# ISA_XILINX.net
KiCad netlist of a schematic drawn in Altium Designer
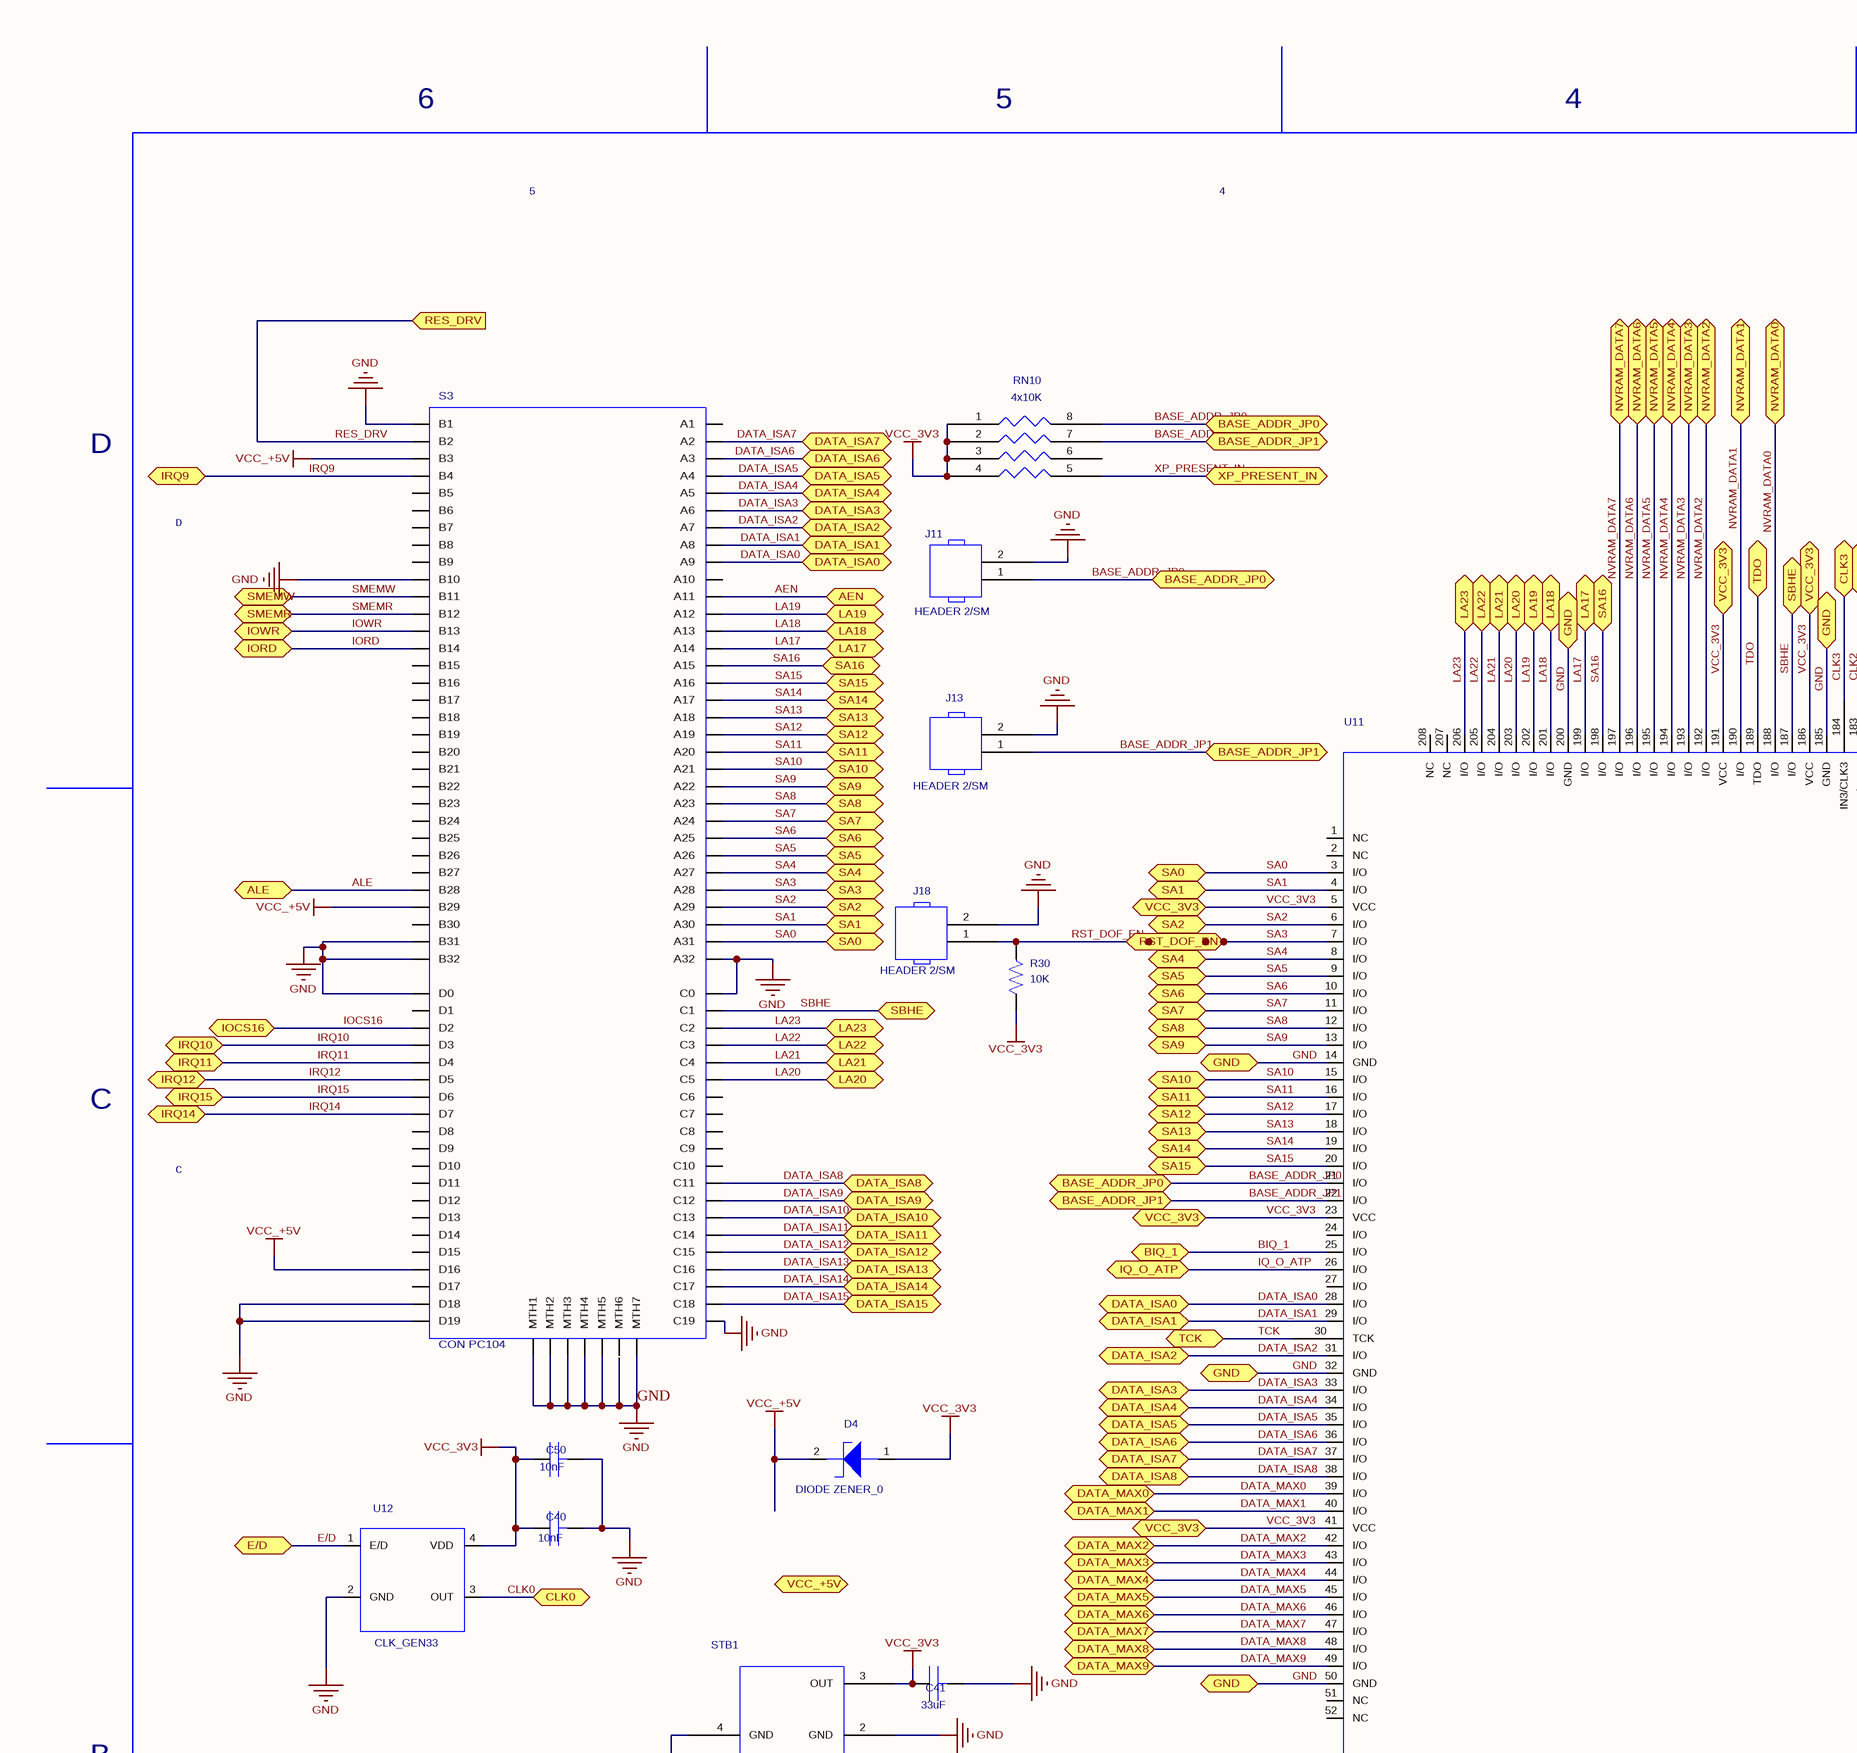
[diagram p0: ISA_XILINX.SchDoc, top left]
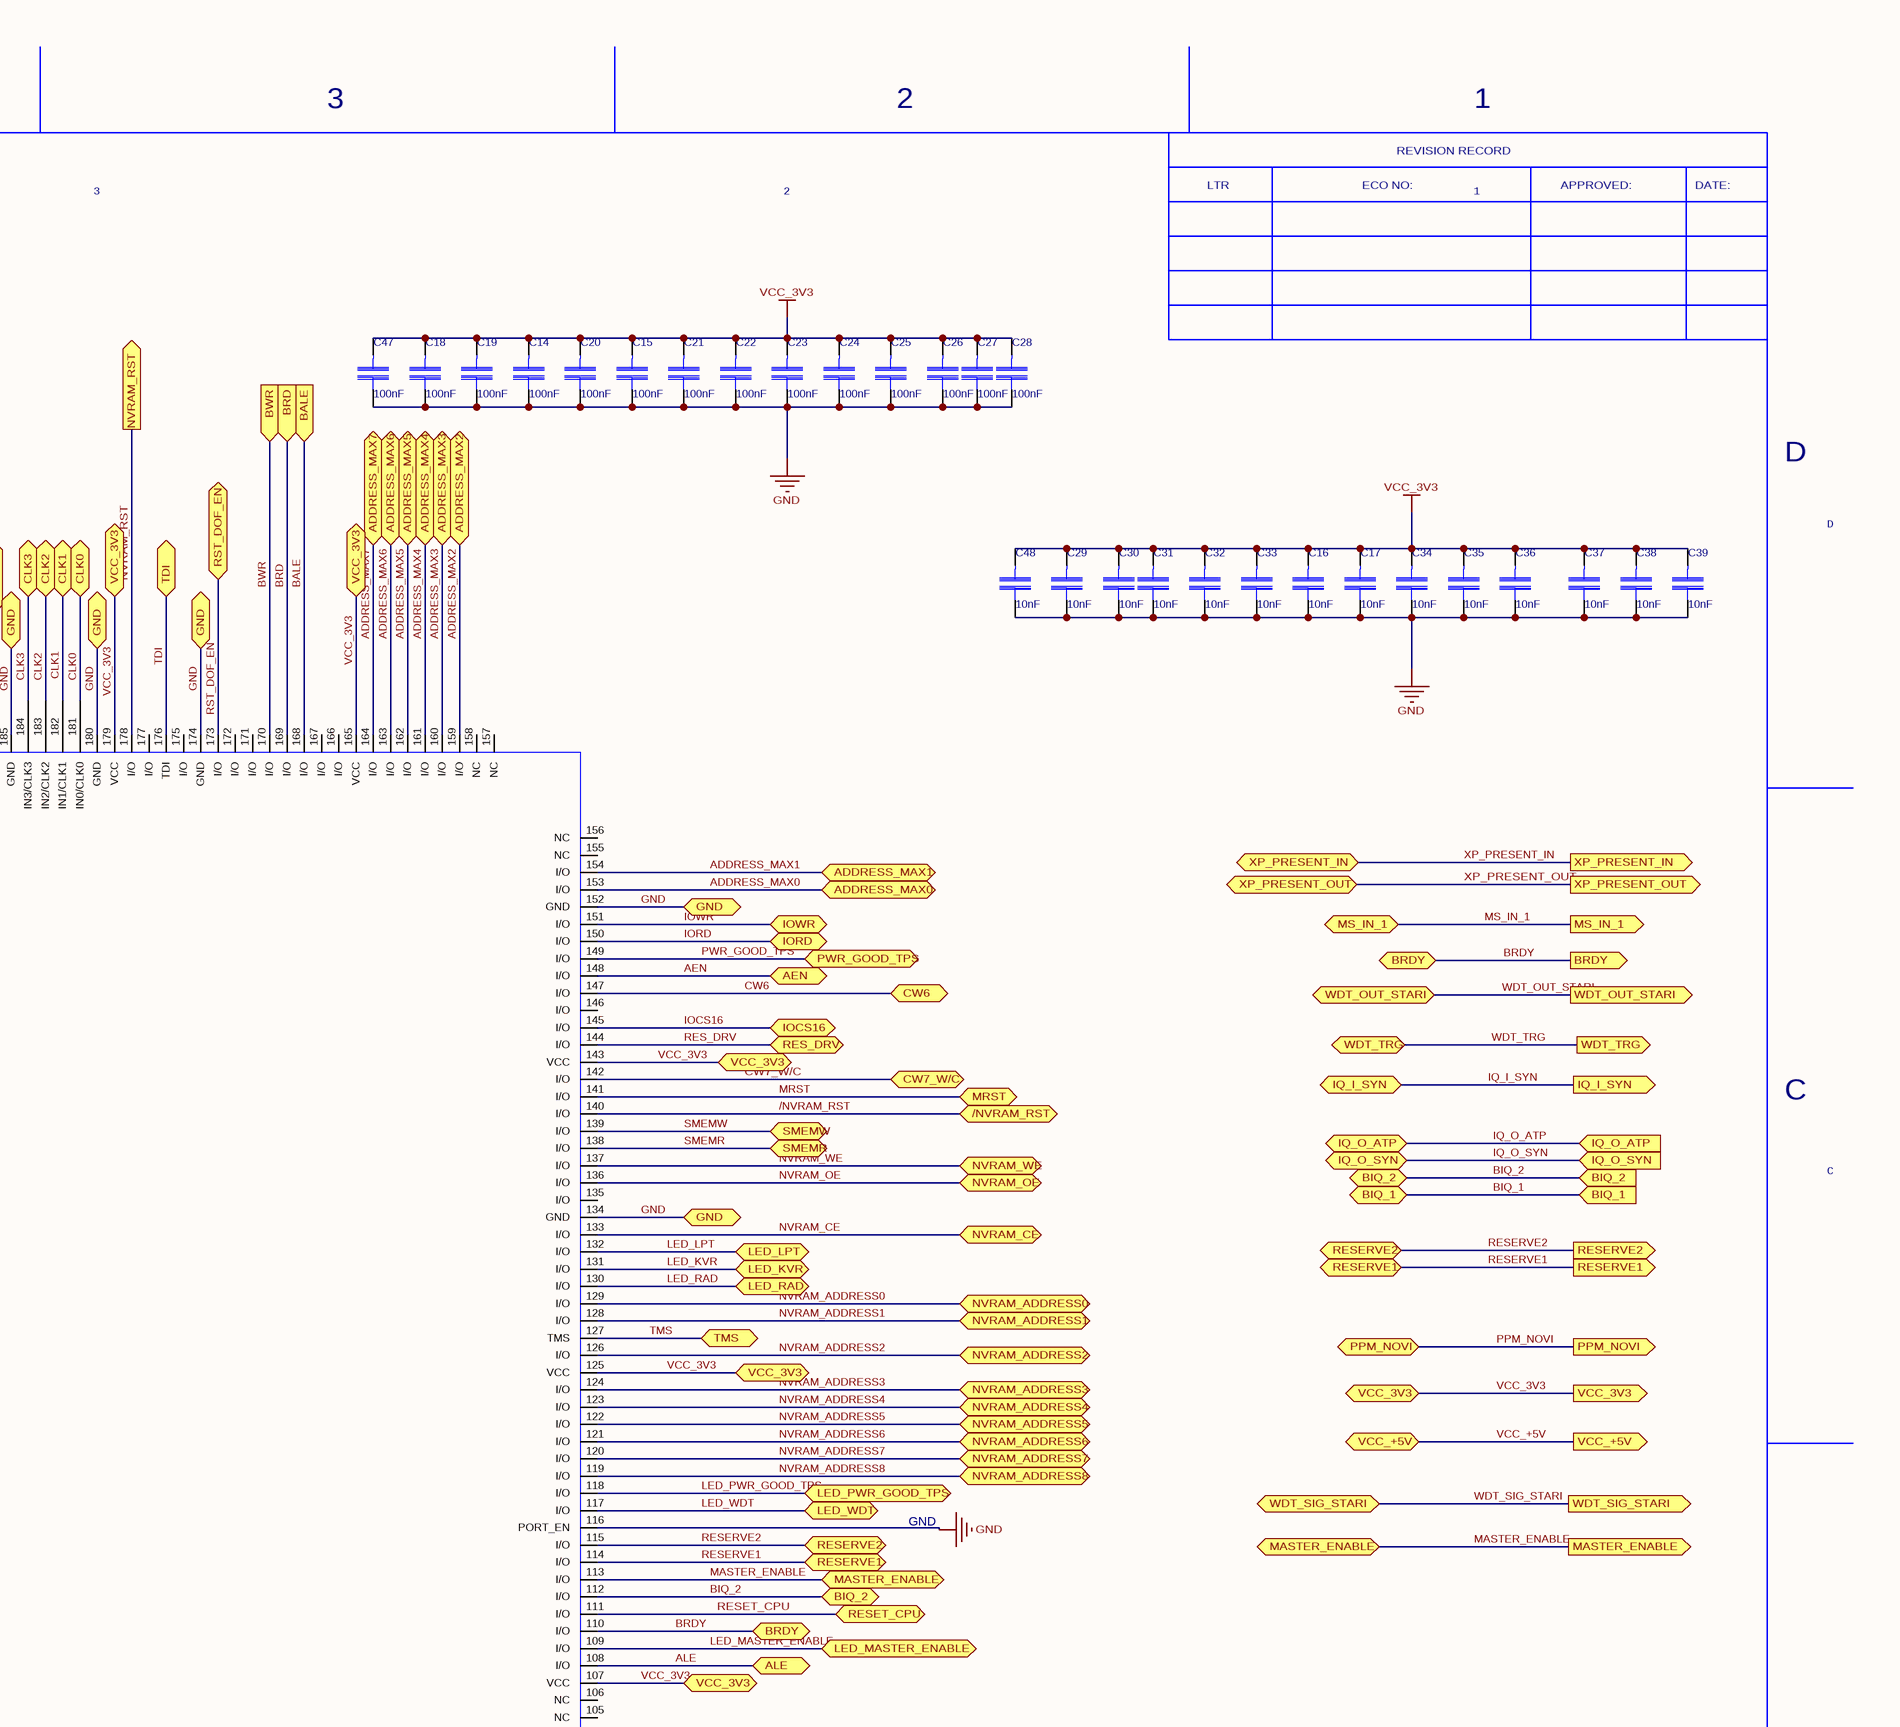
[diagram p1: ISA_XILINX.SchDoc, top right]
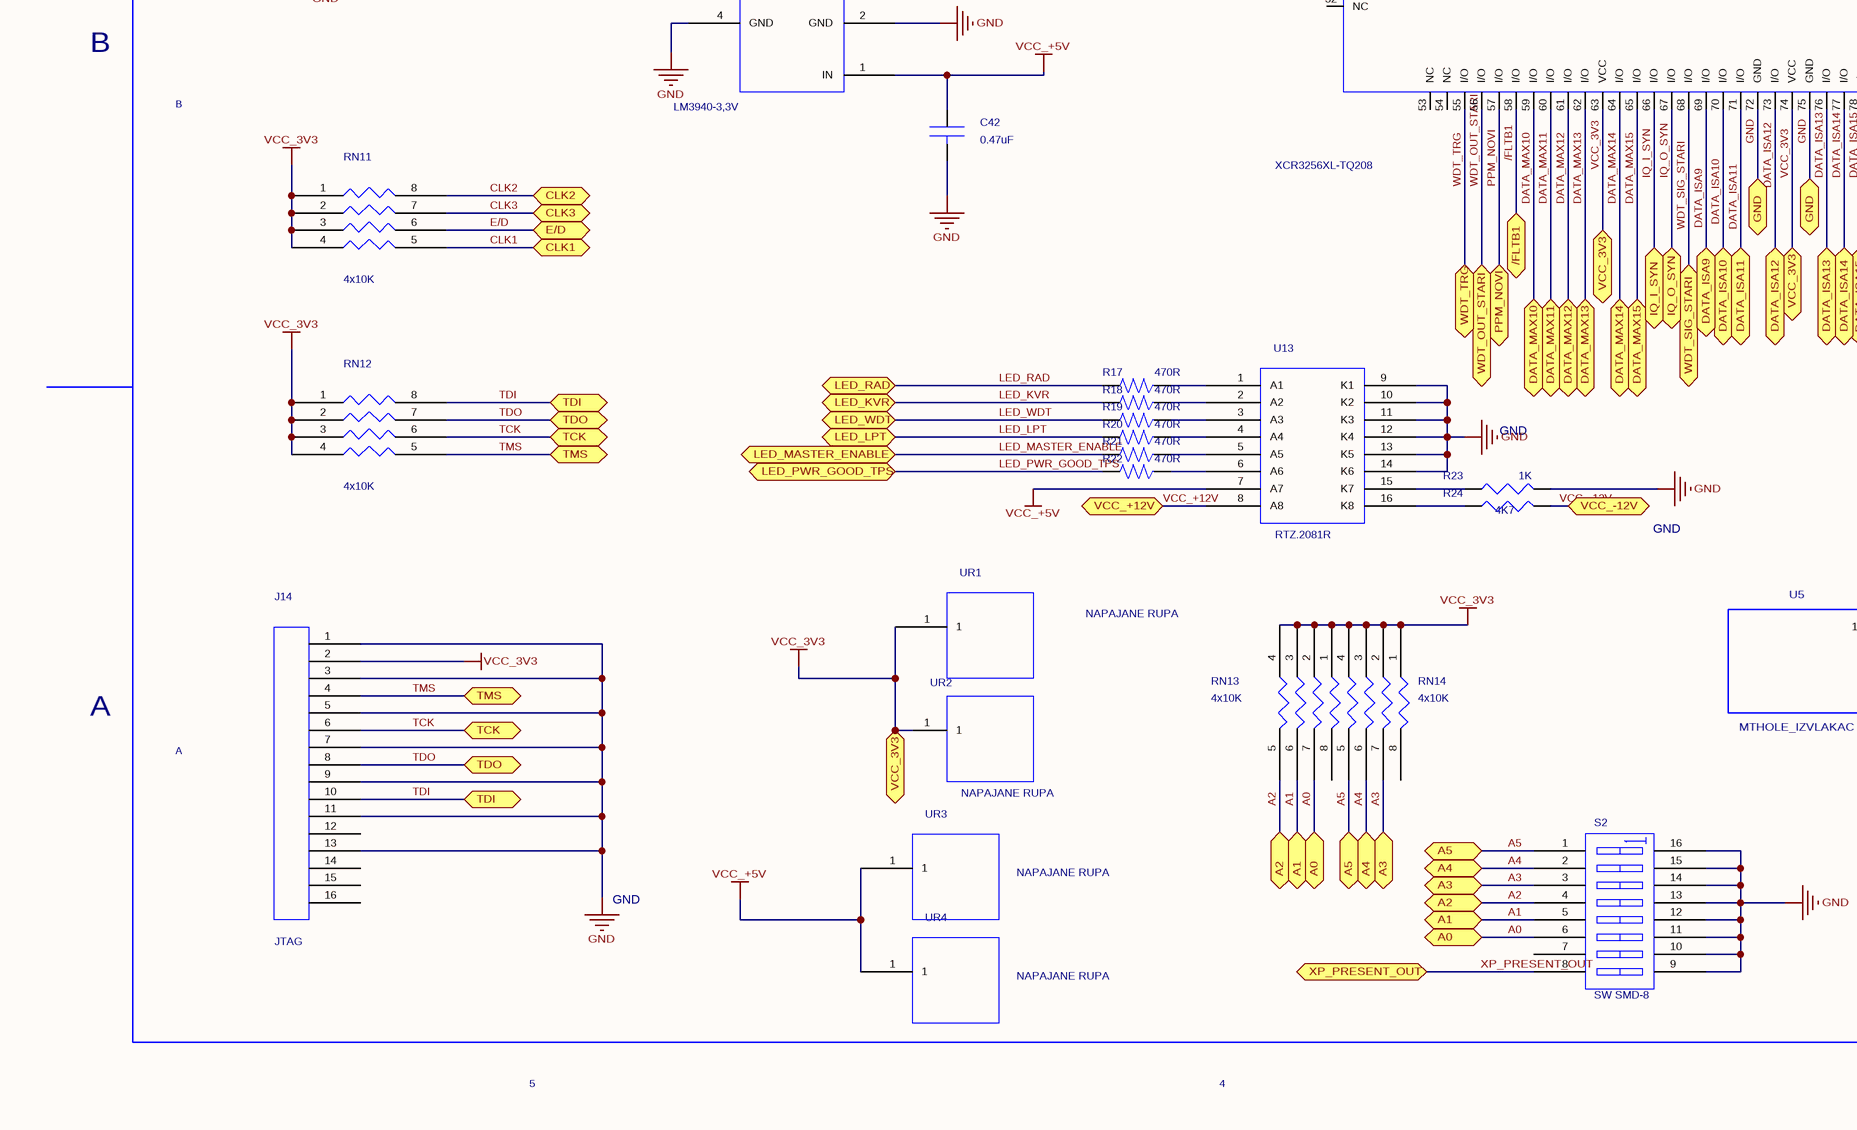
[diagram p2: ISA_XILINX.SchDoc, bottom left]
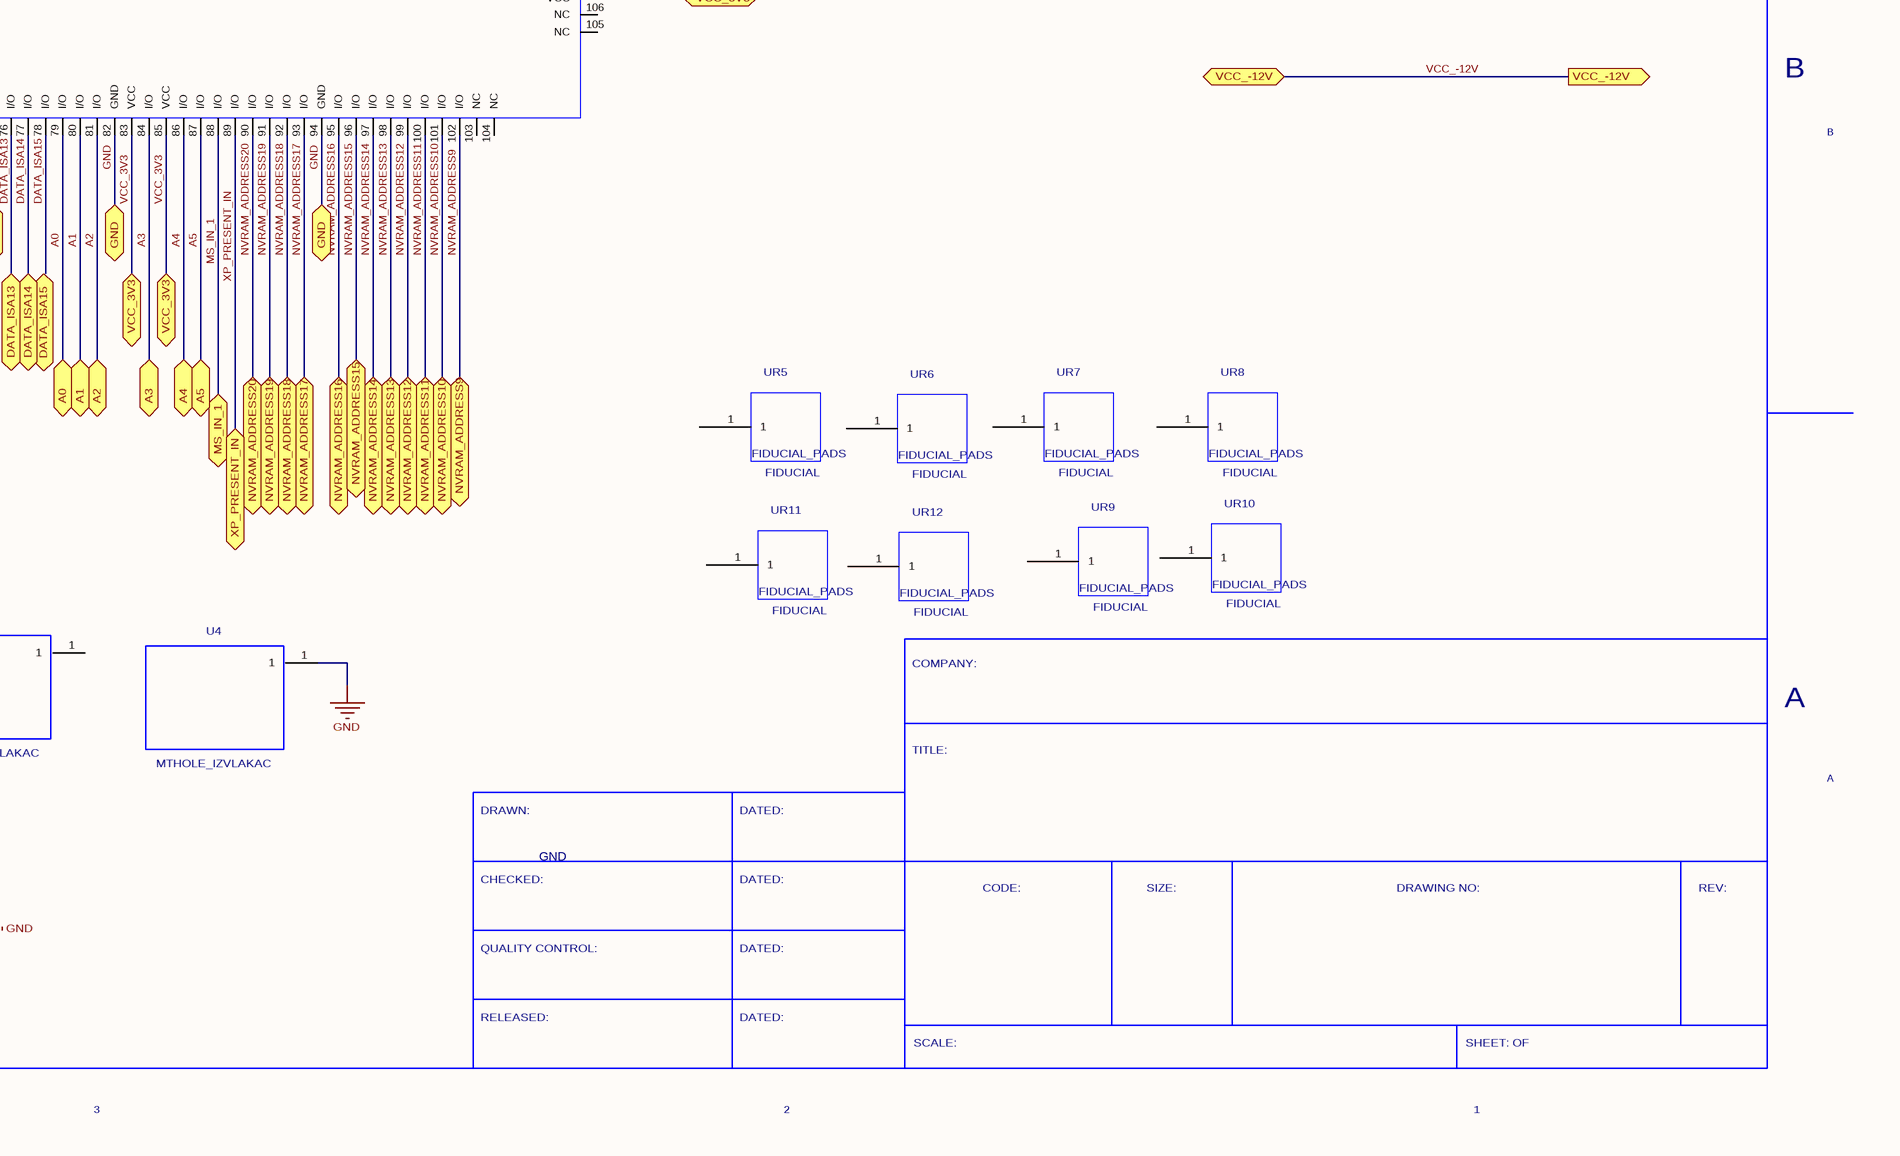
[diagram p3: ISA_XILINX.SchDoc, bottom right]

(export (version "E")
  (design (tool "Eeschema 10.0.6"))
  (components
    (comp (ref "C14")
      (value "100nF")
      (footprint "SM/C_0805")
      (fields (field (name "Comment") "C"))
      (libsource (lib "*") (part "C"))
    )
    (comp (ref "C15")
      (value "100nF")
      (footprint "SM/C_0805")
      (fields (field (name "Comment") "C"))
      (libsource (lib "*") (part "C"))
    )
    (comp (ref "C16")
      (value "10nF")
      (footprint "SM/C_0805")
      (fields (field (name "Comment") "C"))
      (libsource (lib "*") (part "C"))
    )
    (comp (ref "C17")
      (value "10nF")
      (footprint "SM/C_0805")
      (fields (field (name "Comment") "C"))
      (libsource (lib "*") (part "C"))
    )
    (comp (ref "C18")
      (value "100nF")
      (footprint "SM/C_0805")
      (fields (field (name "Comment") "C"))
      (libsource (lib "*") (part "C"))
    )
    (comp (ref "C19")
      (value "100nF")
      (footprint "SM/C_0805")
      (fields (field (name "Comment") "C"))
      (libsource (lib "*") (part "C"))
    )
    (comp (ref "C20")
      (value "100nF")
      (footprint "SM/C_0805")
      (fields (field (name "Comment") "C"))
      (libsource (lib "*") (part "C"))
    )
    (comp (ref "C21")
      (value "100nF")
      (footprint "SM/C_0805")
      (fields (field (name "Comment") "C"))
      (libsource (lib "*") (part "C"))
    )
    (comp (ref "C22")
      (value "100nF")
      (footprint "SM/C_0805")
      (fields (field (name "Comment") "C"))
      (libsource (lib "*") (part "C"))
    )
    (comp (ref "C23")
      (value "100nF")
      (footprint "SM/C_0805")
      (fields (field (name "Comment") "C"))
      (libsource (lib "*") (part "C"))
    )
    (comp (ref "C24")
      (value "100nF")
      (footprint "SM/C_0805")
      (fields (field (name "Comment") "C"))
      (libsource (lib "*") (part "C"))
    )
    (comp (ref "C25")
      (value "100nF")
      (footprint "SM/C_0805")
      (fields (field (name "Comment") "C"))
      (libsource (lib "*") (part "C"))
    )
    (comp (ref "C26")
      (value "100nF")
      (footprint "SM/C_0805")
      (fields (field (name "Comment") "C"))
      (libsource (lib "*") (part "C"))
    )
    (comp (ref "C27")
      (value "100nF")
      (footprint "SM/C_0805")
      (fields (field (name "Comment") "C"))
      (libsource (lib "*") (part "C"))
    )
    (comp (ref "C28")
      (value "100nF")
      (footprint "SM/C_0805")
      (fields (field (name "Comment") "C"))
      (libsource (lib "*") (part "C"))
    )
    (comp (ref "C29")
      (value "10nF")
      (footprint "SM/C_0805")
      (fields (field (name "Comment") "C"))
      (libsource (lib "*") (part "C"))
    )
    (comp (ref "C30")
      (value "10nF")
      (footprint "SM/C_0805")
      (fields (field (name "Comment") "C"))
      (libsource (lib "*") (part "C"))
    )
    (comp (ref "C31")
      (value "10nF")
      (footprint "SM/C_0805")
      (fields (field (name "Comment") "C"))
      (libsource (lib "*") (part "C"))
    )
    (comp (ref "C32")
      (value "10nF")
      (footprint "SM/C_0805")
      (fields (field (name "Comment") "C"))
      (libsource (lib "*") (part "C"))
    )
    (comp (ref "C33")
      (value "10nF")
      (footprint "SM/C_0805")
      (fields (field (name "Comment") "C"))
      (libsource (lib "*") (part "C"))
    )
    (comp (ref "C34")
      (value "10nF")
      (footprint "SM/C_0805")
      (fields (field (name "Comment") "C"))
      (libsource (lib "*") (part "C"))
    )
    (comp (ref "C35")
      (value "10nF")
      (footprint "SM/C_0805")
      (fields (field (name "Comment") "C"))
      (libsource (lib "*") (part "C"))
    )
    (comp (ref "C36")
      (value "10nF")
      (footprint "SM/C_0805")
      (fields (field (name "Comment") "C"))
      (libsource (lib "*") (part "C"))
    )
    (comp (ref "C37")
      (value "10nF")
      (footprint "SM/C_0805")
      (fields (field (name "Comment") "C"))
      (libsource (lib "*") (part "C"))
    )
    (comp (ref "C38")
      (value "10nF")
      (footprint "SM/C_0805")
      (fields (field (name "Comment") "C"))
      (libsource (lib "*") (part "C"))
    )
    (comp (ref "C39")
      (value "10nF")
      (footprint "SM/C_0805")
      (fields (field (name "Comment") "C"))
      (libsource (lib "*") (part "C"))
    )
    (comp (ref "C40")
      (value "10nF")
      (footprint "SM/C_0805")
      (fields (field (name "Comment") "C_4"))
      (libsource (lib "*") (part "C_4"))
    )
    (comp (ref "C41")
      (value "33uF")
      (footprint "CASE_D_MILOS")
      (fields (field (name "Comment") "C_4"))
      (libsource (lib "*") (part "C_4"))
    )
    (comp (ref "C42")
      (value "0.47uF")
      (footprint "CASE_B_MILOS")
      (fields (field (name "Comment") "C_4"))
      (libsource (lib "*") (part "C_4"))
    )
    (comp (ref "C47")
      (value "100nF")
      (footprint "SM/C_0805")
      (fields (field (name "Comment") "C"))
      (libsource (lib "*") (part "C"))
    )
    (comp (ref "C48")
      (value "10nF")
      (footprint "SM/C_0805")
      (fields (field (name "Comment") "C"))
      (libsource (lib "*") (part "C"))
    )
    (comp (ref "C50")
      (value "10nF")
      (footprint "SM/C_0805")
      (fields (field (name "Comment") "C_4"))
      (libsource (lib "*") (part "C_4"))
    )
    (comp (ref "D4")
      (value "DIODE ZENER_0")
      (footprint "BZV55-C3V3")
      (fields (field (name "Comment") "DIODE_ZENER_1"))
      (libsource (lib "*") (part "DIODE_ZENER_1"))
    )
    (comp (ref "J11")
      (value "HEADER 2/SM")
      (footprint "JUMPER_100")
      (fields (field (name "Comment") "HEADER_2/SM"))
      (libsource (lib "*") (part "HEADER_2/SM"))
    )
    (comp (ref "J13")
      (value "HEADER 2/SM")
      (footprint "JUMPER_100")
      (fields (field (name "Comment") "HEADER_2/SM"))
      (libsource (lib "*") (part "HEADER_2/SM"))
    )
    (comp (ref "J14")
      (value "JTAG")
      (footprint "JTAG_SMD_REV2")
      (fields (field (name "Comment") "CONN_FLEX_16/SM"))
      (libsource (lib "*") (part "CONN_FLEX_16/SM"))
    )
    (comp (ref "J18")
      (value "HEADER 2/SM")
      (footprint "JUMPER_100")
      (fields (field (name "Comment") "HEADER_2/SM"))
      (libsource (lib "*") (part "HEADER_2/SM"))
    )
    (comp (ref "R17")
      (value "470R")
      (footprint "SM/R_1206")
      (fields (field (name "VOLTAGE") "RVMAX") (field (name "POWER") "RMAX") (field (name "Comment") "R"))
      (libsource (lib "*") (part "R"))
    )
    (comp (ref "R18")
      (value "470R")
      (footprint "SM/R_1206")
      (fields (field (name "VOLTAGE") "RVMAX") (field (name "POWER") "RMAX") (field (name "Comment") "R"))
      (libsource (lib "*") (part "R"))
    )
    (comp (ref "R19")
      (value "470R")
      (footprint "SM/R_1206")
      (fields (field (name "VOLTAGE") "RVMAX") (field (name "POWER") "RMAX") (field (name "Comment") "R"))
      (libsource (lib "*") (part "R"))
    )
    (comp (ref "R20")
      (value "470R")
      (footprint "SM/R_1206")
      (fields (field (name "VOLTAGE") "RVMAX") (field (name "POWER") "RMAX") (field (name "Comment") "R"))
      (libsource (lib "*") (part "R"))
    )
    (comp (ref "R21")
      (value "470R")
      (footprint "SM/R_1206")
      (fields (field (name "VOLTAGE") "RVMAX") (field (name "POWER") "RMAX") (field (name "Comment") "R"))
      (libsource (lib "*") (part "R"))
    )
    (comp (ref "R22")
      (value "470R")
      (footprint "SM/R_1206")
      (fields (field (name "VOLTAGE") "RVMAX") (field (name "POWER") "RMAX") (field (name "Comment") "R"))
      (libsource (lib "*") (part "R"))
    )
    (comp (ref "R23")
      (value "1K")
      (footprint "SM/R_1206")
      (fields (field (name "Comment") "RESISTOR_2"))
      (libsource (lib "*") (part "RESISTOR_2"))
    )
    (comp (ref "R24")
      (value "4K7")
      (footprint "SM/R_1206")
      (fields (field (name "Comment") "RESISTOR_2"))
      (libsource (lib "*") (part "RESISTOR_2"))
    )
    (comp (ref "R30")
      (value "10K")
      (footprint "SM/R_1206")
      (fields (field (name "VOLTAGE") "RVMAX") (field (name "POWER") "RMAX") (field (name "Comment") "R"))
      (libsource (lib "*") (part "R"))
    )
    (comp (ref "RN10")
      (value "4x10K")
      (footprint "SMD_RX4")
      (fields (field (name "Comment") "RESAR_IS_4/SM"))
      (libsource (lib "*") (part "RESAR_IS_4/SM"))
    )
    (comp (ref "RN11")
      (value "4x10K")
      (footprint "SMD_RX4")
      (fields (field (name "Comment") "RESAR_IS_4/SM"))
      (libsource (lib "*") (part "RESAR_IS_4/SM"))
    )
    (comp (ref "RN12")
      (value "4x10K")
      (footprint "SMD_RX4")
      (fields (field (name "Comment") "RESAR_IS_4/SM"))
      (libsource (lib "*") (part "RESAR_IS_4/SM"))
    )
    (comp (ref "RN13")
      (value "4x10K")
      (footprint "SMD_RX4")
      (fields (field (name "Comment") "RESAR_IS_4/SM"))
      (libsource (lib "*") (part "RESAR_IS_4/SM"))
    )
    (comp (ref "RN14")
      (value "4x10K")
      (footprint "SMD_RX4")
      (fields (field (name "Comment") "RESAR_IS_4/SM"))
      (libsource (lib "*") (part "RESAR_IS_4/SM"))
    )
    (comp (ref "S2")
      (value "SW SMD-8")
      (footprint "SMD_DIPSW_100")
      (fields (field (name "Comment") "SW_DIP-8"))
      (libsource (lib "*") (part "SW_DIP-8"))
    )
    (comp (ref "S3")
      (value "CON PC104")
      (footprint "WAFER_PADS_REV2")
      (fields (field (name "Comment") "CON_EISAE_0"))
      (libsource (lib "ATLAS_XP2V5.2016.11.14") (part "CON_EISAE_0"))
    )
    (comp (ref "STB1")
      (value "LM3940-3,3V")
      (footprint "TO263AA_GND_PLANE_REV1")
      (fields (field (name "Comment") "LM3940-3_3V"))
      (libsource (lib "*") (part "LM3940-3_3V"))
    )
    (comp (ref "U4")
      (value "MTHOLE_IZVLAKAC")
      (footprint "MTH_IZVLAKAC_PADS")
      (description "Rupa za Rittal-ov izvlakac")
      (libsource (lib "*") (part "MTHOLE_IZVLAKAC"))
    )
    (comp (ref "U5")
      (value "MTHOLE_IZVLAKAC")
      (footprint "MTH_IZVLAKAC_PADS")
      (description "Rupa za Rittal-ov izvlakac")
      (libsource (lib "*") (part "MTHOLE_IZVLAKAC"))
    )
    (comp (ref "U11")
      (value "XCR3256XL-TQ208")
      (footprint "QUAD.50M/208/WG30.60")
      (libsource (lib "*") (part "XCR3256XL-TQ208"))
    )
    (comp (ref "U12")
      (value "CLK_GEN33")
      (footprint "CLK_GEN33_REV1")
      (libsource (lib "*") (part "CLK_GEN33"))
    )
    (comp (ref "U13")
      (value "RTZ.2081R")
      (footprint "LED_8_REV3_PADS")
      (description "LED8x1")
      (fields (field (name "Comment") "LED8X1"))
      (libsource (lib "*") (part "LED8X1"))
    )
    (comp (ref "UR1")
      (value "NAPAJANE RUPA")
      (footprint "NAPAJANJE_RUPA_REV1")
      (fields (field (name "Comment") "NAPAJANE_RUPA"))
      (libsource (lib "*") (part "NAPAJANE_RUPA"))
    )
    (comp (ref "UR2")
      (value "NAPAJANE RUPA")
      (footprint "NAPAJANJE_RUPA_REV1")
      (fields (field (name "Comment") "NAPAJANE_RUPA"))
      (libsource (lib "*") (part "NAPAJANE_RUPA"))
    )
    (comp (ref "UR3")
      (value "NAPAJANE RUPA")
      (footprint "NAPAJANJE_RUPA_REV1")
      (fields (field (name "Comment") "NAPAJANE_RUPA"))
      (libsource (lib "*") (part "NAPAJANE_RUPA"))
    )
    (comp (ref "UR4")
      (value "NAPAJANE RUPA")
      (footprint "NAPAJANJE_RUPA_REV1")
      (fields (field (name "Comment") "NAPAJANE_RUPA"))
      (libsource (lib "*") (part "NAPAJANE_RUPA"))
    )
    (comp (ref "UR5")
      (value "FIDUCIAL_PADS")
      (footprint "FIDUCIAL_R_TOP")
      (fields (field (name "ALTIUM_VALUE") "FIDUCIAL"))
      (libsource (lib "*") (part "FIDUCIAL_PADS"))
    )
    (comp (ref "UR6")
      (value "FIDUCIAL_PADS")
      (footprint "FIDUCIAL_R_TOP")
      (fields (field (name "ALTIUM_VALUE") "FIDUCIAL"))
      (libsource (lib "*") (part "FIDUCIAL_PADS"))
    )
    (comp (ref "UR7")
      (value "FIDUCIAL_PADS")
      (footprint "FIDUCIAL_R_TOP")
      (fields (field (name "ALTIUM_VALUE") "FIDUCIAL"))
      (libsource (lib "*") (part "FIDUCIAL_PADS"))
    )
    (comp (ref "UR8")
      (value "FIDUCIAL_PADS")
      (footprint "FIDUCIAL_R_TOP")
      (fields (field (name "ALTIUM_VALUE") "FIDUCIAL"))
      (libsource (lib "*") (part "FIDUCIAL_PADS"))
    )
    (comp (ref "UR9")
      (value "FIDUCIAL_PADS")
      (footprint "FIDUCIAL_R_TOP")
      (fields (field (name "ALTIUM_VALUE") "FIDUCIAL"))
      (libsource (lib "*") (part "FIDUCIAL_PADS"))
    )
    (comp (ref "UR10")
      (value "FIDUCIAL_PADS")
      (footprint "FIDUCIAL_R_TOP")
      (fields (field (name "ALTIUM_VALUE") "FIDUCIAL"))
      (libsource (lib "*") (part "FIDUCIAL_PADS"))
    )
    (comp (ref "UR11")
      (value "FIDUCIAL_PADS")
      (footprint "FIDUCIAL_R_TOP")
      (fields (field (name "ALTIUM_VALUE") "FIDUCIAL"))
      (libsource (lib "*") (part "FIDUCIAL_PADS"))
    )
    (comp (ref "UR12")
      (value "FIDUCIAL_PADS")
      (footprint "FIDUCIAL_R_TOP")
      (fields (field (name "ALTIUM_VALUE") "FIDUCIAL"))
      (libsource (lib "*") (part "FIDUCIAL_PADS"))
    )
  )
  (nets
    (net (code "1") (name "/A0") (class "Default")
      (node (ref "RN13") (pin "7") (pinfunction "7_7") (pintype "passive"))
      (node (ref "S2") (pin "6") (pinfunction "A6_6") (pintype "passive"))
      (node (ref "U11") (pin "79") (pinfunction "I/O_79") (pintype "bidirectional"))
    )
    (net (code "2") (name "/A1") (class "Default")
      (node (ref "RN13") (pin "6") (pinfunction "6_6") (pintype "passive"))
      (node (ref "S2") (pin "5") (pinfunction "A5_5") (pintype "passive"))
      (node (ref "U11") (pin "80") (pinfunction "I/O_80") (pintype "bidirectional"))
    )
    (net (code "3") (name "/A2") (class "Default")
      (node (ref "RN13") (pin "5") (pinfunction "5_5") (pintype "passive"))
      (node (ref "S2") (pin "4") (pinfunction "A4_4") (pintype "passive"))
      (node (ref "U11") (pin "81") (pinfunction "I/O_81") (pintype "bidirectional"))
    )
    (net (code "4") (name "/A3") (class "Default")
      (node (ref "RN14") (pin "7") (pinfunction "7_7") (pintype "passive"))
      (node (ref "S2") (pin "3") (pinfunction "A3_3") (pintype "passive"))
      (node (ref "U11") (pin "84") (pinfunction "I/O_84") (pintype "bidirectional"))
    )
    (net (code "5") (name "/A4") (class "Default")
      (node (ref "RN14") (pin "6") (pinfunction "6_6") (pintype "passive"))
      (node (ref "S2") (pin "2") (pinfunction "A2_2") (pintype "passive"))
      (node (ref "U11") (pin "86") (pinfunction "I/O_86") (pintype "bidirectional"))
    )
    (net (code "6") (name "/A5") (class "Default")
      (node (ref "RN14") (pin "5") (pinfunction "5_5") (pintype "passive"))
      (node (ref "S2") (pin "1") (pinfunction "A1_1") (pintype "passive"))
      (node (ref "U11") (pin "87") (pinfunction "I/O_87") (pintype "bidirectional"))
    )
    (net (code "7") (name "/ADDRESS_MAX0") (class "Default")
      (node (ref "U11") (pin "153") (pinfunction "I/O_153") (pintype "bidirectional"))
    )
    (net (code "8") (name "/ADDRESS_MAX1") (class "Default")
      (node (ref "U11") (pin "154") (pinfunction "I/O_154") (pintype "bidirectional"))
    )
    (net (code "9") (name "/ADDRESS_MAX2") (class "Default")
      (node (ref "U11") (pin "159") (pinfunction "I/O_159") (pintype "bidirectional"))
    )
    (net (code "10") (name "/ADDRESS_MAX3") (class "Default")
      (node (ref "U11") (pin "160") (pinfunction "I/O_160") (pintype "bidirectional"))
    )
    (net (code "11") (name "/ADDRESS_MAX4") (class "Default")
      (node (ref "U11") (pin "161") (pinfunction "I/O_161") (pintype "bidirectional"))
    )
    (net (code "12") (name "/ADDRESS_MAX5") (class "Default")
      (node (ref "U11") (pin "162") (pinfunction "I/O_162") (pintype "bidirectional"))
    )
    (net (code "13") (name "/ADDRESS_MAX6") (class "Default")
      (node (ref "U11") (pin "163") (pinfunction "I/O_163") (pintype "bidirectional"))
    )
    (net (code "14") (name "/ADDRESS_MAX7") (class "Default")
      (node (ref "U11") (pin "164") (pinfunction "I/O_164") (pintype "bidirectional"))
    )
    (net (code "15") (name "/AEN") (class "Default")
      (node (ref "S3") (pin "A11") (pinfunction "A11_A11") (pintype "passive"))
      (node (ref "U11") (pin "148") (pinfunction "I/O_148") (pintype "bidirectional"))
    )
    (net (code "16") (name "/ALE") (class "Default")
      (node (ref "S3") (pin "B28") (pinfunction "B28_B28") (pintype "passive"))
      (node (ref "U11") (pin "108") (pinfunction "I/O_108") (pintype "bidirectional"))
    )
    (net (code "17") (name "/BALE") (class "Default")
      (node (ref "U11") (pin "168") (pinfunction "I/O_168") (pintype "bidirectional"))
    )
    (net (code "18") (name "/BASE_ADDR_JP0") (class "Default")
      (node (ref "J11") (pin "1") (pinfunction "1_1") (pintype "passive"))
      (node (ref "RN10") (pin "8") (pinfunction "8_8") (pintype "passive"))
      (node (ref "U11") (pin "21") (pinfunction "I/O_21") (pintype "bidirectional"))
    )
    (net (code "19") (name "/BASE_ADDR_JP1") (class "Default")
      (node (ref "J13") (pin "1") (pinfunction "1_1") (pintype "passive"))
      (node (ref "RN10") (pin "7") (pinfunction "7_7") (pintype "passive"))
      (node (ref "U11") (pin "22") (pinfunction "I/O_22") (pintype "bidirectional"))
    )
    (net (code "20") (name "/BIQ_1") (class "Default")
      (node (ref "U11") (pin "25") (pinfunction "I/O_25") (pintype "bidirectional"))
    )
    (net (code "21") (name "/BIQ_2") (class "Default")
      (node (ref "U11") (pin "112") (pinfunction "I/O_112") (pintype "bidirectional"))
    )
    (net (code "22") (name "/BRD") (class "Default")
      (node (ref "U11") (pin "169") (pinfunction "I/O_169") (pintype "bidirectional"))
    )
    (net (code "23") (name "/BRDY") (class "Default")
      (node (ref "U11") (pin "110") (pinfunction "I/O_110") (pintype "bidirectional"))
    )
    (net (code "24") (name "/BWR") (class "Default")
      (node (ref "U11") (pin "170") (pinfunction "I/O_170") (pintype "bidirectional"))
    )
    (net (code "25") (name "/CLK0") (class "Default")
      (node (ref "U11") (pin "181") (pinfunction "IN0/CLK0_181") (pintype "passive"))
      (node (ref "U12") (pin "3") (pinfunction "OUT_3") (pintype "passive"))
    )
    (net (code "26") (name "/CLK1") (class "Default")
      (node (ref "RN11") (pin "5") (pinfunction "5_5") (pintype "passive"))
      (node (ref "U11") (pin "182") (pinfunction "IN1/CLK1_182") (pintype "passive"))
    )
    (net (code "27") (name "/CLK2") (class "Default")
      (node (ref "RN11") (pin "8") (pinfunction "8_8") (pintype "passive"))
      (node (ref "U11") (pin "183") (pinfunction "IN2/CLK2_183") (pintype "passive"))
    )
    (net (code "28") (name "/CLK3") (class "Default")
      (node (ref "RN11") (pin "7") (pinfunction "7_7") (pintype "passive"))
      (node (ref "U11") (pin "184") (pinfunction "IN3/CLK3_184") (pintype "passive"))
    )
    (net (code "29") (name "/CW6") (class "Default")
      (node (ref "U11") (pin "147") (pinfunction "I/O_147") (pintype "bidirectional"))
    )
    (net (code "30") (name "/CW7_W{slash}C") (class "Default")
      (node (ref "U11") (pin "142") (pinfunction "I/O_142") (pintype "bidirectional"))
    )
    (net (code "31") (name "/DATA_ISA0") (class "Default")
      (node (ref "S3") (pin "A9") (pinfunction "A9_A9") (pintype "passive"))
      (node (ref "U11") (pin "28") (pinfunction "I/O_28") (pintype "bidirectional"))
    )
    (net (code "32") (name "/DATA_ISA1") (class "Default")
      (node (ref "S3") (pin "A8") (pinfunction "A8_A8") (pintype "passive"))
      (node (ref "U11") (pin "29") (pinfunction "I/O_29") (pintype "bidirectional"))
    )
    (net (code "33") (name "/DATA_ISA2") (class "Default")
      (node (ref "S3") (pin "A7") (pinfunction "A7_A7") (pintype "passive"))
      (node (ref "U11") (pin "31") (pinfunction "I/O_31") (pintype "bidirectional"))
    )
    (net (code "34") (name "/DATA_ISA3") (class "Default")
      (node (ref "S3") (pin "A6") (pinfunction "A6_A6") (pintype "passive"))
      (node (ref "U11") (pin "33") (pinfunction "I/O_33") (pintype "bidirectional"))
    )
    (net (code "35") (name "/DATA_ISA4") (class "Default")
      (node (ref "S3") (pin "A5") (pinfunction "A5_A5") (pintype "passive"))
      (node (ref "U11") (pin "34") (pinfunction "I/O_34") (pintype "bidirectional"))
    )
    (net (code "36") (name "/DATA_ISA5") (class "Default")
      (node (ref "S3") (pin "A4") (pinfunction "A4_A4") (pintype "passive"))
      (node (ref "U11") (pin "35") (pinfunction "I/O_35") (pintype "bidirectional"))
    )
    (net (code "37") (name "/DATA_ISA6") (class "Default")
      (node (ref "S3") (pin "A3") (pinfunction "A3_A3") (pintype "passive"))
      (node (ref "U11") (pin "36") (pinfunction "I/O_36") (pintype "bidirectional"))
    )
    (net (code "38") (name "/DATA_ISA7") (class "Default")
      (node (ref "S3") (pin "A2") (pinfunction "A2_A2") (pintype "passive"))
      (node (ref "U11") (pin "37") (pinfunction "I/O_37") (pintype "bidirectional"))
    )
    (net (code "39") (name "/DATA_ISA8") (class "Default")
      (node (ref "S3") (pin "C11") (pinfunction "C11_C11") (pintype "passive"))
      (node (ref "U11") (pin "38") (pinfunction "I/O_38") (pintype "bidirectional"))
    )
    (net (code "40") (name "/DATA_ISA9") (class "Default")
      (node (ref "S3") (pin "C12") (pinfunction "C12_C12") (pintype "passive"))
      (node (ref "U11") (pin "69") (pinfunction "I/O_69") (pintype "bidirectional"))
    )
    (net (code "41") (name "/DATA_ISA10") (class "Default")
      (node (ref "S3") (pin "C13") (pinfunction "C13_C13") (pintype "passive"))
      (node (ref "U11") (pin "70") (pinfunction "I/O_70") (pintype "bidirectional"))
    )
    (net (code "42") (name "/DATA_ISA11") (class "Default")
      (node (ref "S3") (pin "C14") (pinfunction "C14_C14") (pintype "passive"))
      (node (ref "U11") (pin "71") (pinfunction "I/O_71") (pintype "bidirectional"))
    )
    (net (code "43") (name "/DATA_ISA12") (class "Default")
      (node (ref "S3") (pin "C15") (pinfunction "C15_C15") (pintype "passive"))
      (node (ref "U11") (pin "73") (pinfunction "I/O_73") (pintype "bidirectional"))
    )
    (net (code "44") (name "/DATA_ISA13") (class "Default")
      (node (ref "S3") (pin "C16") (pinfunction "C16_C16") (pintype "passive"))
      (node (ref "U11") (pin "76") (pinfunction "I/O_76") (pintype "bidirectional"))
    )
    (net (code "45") (name "/DATA_ISA14") (class "Default")
      (node (ref "S3") (pin "C17") (pinfunction "C17_C17") (pintype "passive"))
      (node (ref "U11") (pin "77") (pinfunction "I/O_77") (pintype "bidirectional"))
    )
    (net (code "46") (name "/DATA_ISA15") (class "Default")
      (node (ref "S3") (pin "C18") (pinfunction "C18_C18") (pintype "passive"))
      (node (ref "U11") (pin "78") (pinfunction "I/O_78") (pintype "bidirectional"))
    )
    (net (code "47") (name "/DATA_MAX0") (class "Default")
      (node (ref "U11") (pin "39") (pinfunction "I/O_39") (pintype "bidirectional"))
    )
    (net (code "48") (name "/DATA_MAX1") (class "Default")
      (node (ref "U11") (pin "40") (pinfunction "I/O_40") (pintype "bidirectional"))
    )
    (net (code "49") (name "/DATA_MAX2") (class "Default")
      (node (ref "U11") (pin "42") (pinfunction "I/O_42") (pintype "bidirectional"))
    )
    (net (code "50") (name "/DATA_MAX3") (class "Default")
      (node (ref "U11") (pin "43") (pinfunction "I/O_43") (pintype "bidirectional"))
    )
    (net (code "51") (name "/DATA_MAX4") (class "Default")
      (node (ref "U11") (pin "44") (pinfunction "I/O_44") (pintype "bidirectional"))
    )
    (net (code "52") (name "/DATA_MAX5") (class "Default")
      (node (ref "U11") (pin "45") (pinfunction "I/O_45") (pintype "bidirectional"))
    )
    (net (code "53") (name "/DATA_MAX6") (class "Default")
      (node (ref "U11") (pin "46") (pinfunction "I/O_46") (pintype "bidirectional"))
    )
    (net (code "54") (name "/DATA_MAX7") (class "Default")
      (node (ref "U11") (pin "47") (pinfunction "I/O_47") (pintype "bidirectional"))
    )
    (net (code "55") (name "/DATA_MAX8") (class "Default")
      (node (ref "U11") (pin "48") (pinfunction "I/O_48") (pintype "bidirectional"))
    )
    (net (code "56") (name "/DATA_MAX9") (class "Default")
      (node (ref "U11") (pin "49") (pinfunction "I/O_49") (pintype "bidirectional"))
    )
    (net (code "57") (name "/DATA_MAX10") (class "Default")
      (node (ref "U11") (pin "59") (pinfunction "I/O_59") (pintype "bidirectional"))
    )
    (net (code "58") (name "/DATA_MAX11") (class "Default")
      (node (ref "U11") (pin "60") (pinfunction "I/O_60") (pintype "bidirectional"))
    )
    (net (code "59") (name "/DATA_MAX12") (class "Default")
      (node (ref "U11") (pin "61") (pinfunction "I/O_61") (pintype "bidirectional"))
    )
    (net (code "60") (name "/DATA_MAX13") (class "Default")
      (node (ref "U11") (pin "62") (pinfunction "I/O_62") (pintype "bidirectional"))
    )
    (net (code "61") (name "/DATA_MAX14") (class "Default")
      (node (ref "U11") (pin "64") (pinfunction "I/O_64") (pintype "bidirectional"))
    )
    (net (code "62") (name "/DATA_MAX15") (class "Default")
      (node (ref "U11") (pin "65") (pinfunction "I/O_65") (pintype "bidirectional"))
    )
    (net (code "63") (name "/E{slash}D") (class "Default")
      (node (ref "RN11") (pin "6") (pinfunction "6_6") (pintype "passive"))
      (node (ref "U12") (pin "1") (pinfunction "E/D_1") (pintype "passive"))
    )
    (net (code "64") (name "/IOCS16") (class "Default")
      (node (ref "S3") (pin "D2") (pinfunction "D2_D2") (pintype "passive"))
      (node (ref "U11") (pin "145") (pinfunction "I/O_145") (pintype "bidirectional"))
    )
    (net (code "65") (name "/IORD") (class "Default")
      (node (ref "S3") (pin "B14") (pinfunction "B14_B14") (pintype "passive"))
      (node (ref "U11") (pin "150") (pinfunction "I/O_150") (pintype "bidirectional"))
    )
    (net (code "66") (name "/IOWR") (class "Default")
      (node (ref "S3") (pin "B13") (pinfunction "B13_B13") (pintype "passive"))
      (node (ref "U11") (pin "151") (pinfunction "I/O_151") (pintype "bidirectional"))
    )
    (net (code "67") (name "/IQ_I_SYN") (class "Default")
      (node (ref "U11") (pin "66") (pinfunction "I/O_66") (pintype "bidirectional"))
    )
    (net (code "68") (name "/IQ_O_ATP") (class "Default")
      (node (ref "U11") (pin "26") (pinfunction "I/O_26") (pintype "bidirectional"))
    )
    (net (code "69") (name "/IQ_O_SYN") (class "Default")
      (node (ref "U11") (pin "67") (pinfunction "I/O_67") (pintype "bidirectional"))
    )
    (net (code "70") (name "/IRQ9") (class "Default")
      (node (ref "S3") (pin "B4") (pinfunction "B4_B4") (pintype "passive"))
    )
    (net (code "71") (name "/IRQ10") (class "Default")
      (node (ref "S3") (pin "D3") (pinfunction "D3_D3") (pintype "passive"))
    )
    (net (code "72") (name "/IRQ11") (class "Default")
      (node (ref "S3") (pin "D4") (pinfunction "D4_D4") (pintype "passive"))
    )
    (net (code "73") (name "/IRQ12") (class "Default")
      (node (ref "S3") (pin "D5") (pinfunction "D5_D5") (pintype "passive"))
    )
    (net (code "74") (name "/IRQ14") (class "Default")
      (node (ref "S3") (pin "D7") (pinfunction "D7_D7") (pintype "passive"))
    )
    (net (code "75") (name "/IRQ15") (class "Default")
      (node (ref "S3") (pin "D6") (pinfunction "D6_D6") (pintype "passive"))
    )
    (net (code "76") (name "/LA17") (class "Default")
      (node (ref "S3") (pin "A14") (pinfunction "A14_A14") (pintype "passive"))
      (node (ref "U11") (pin "199") (pinfunction "I/O_199") (pintype "bidirectional"))
    )
    (net (code "77") (name "/LA18") (class "Default")
      (node (ref "S3") (pin "A13") (pinfunction "A13_A13") (pintype "passive"))
      (node (ref "U11") (pin "201") (pinfunction "I/O_201") (pintype "bidirectional"))
    )
    (net (code "78") (name "/LA19") (class "Default")
      (node (ref "S3") (pin "A12") (pinfunction "A12_A12") (pintype "passive"))
      (node (ref "U11") (pin "202") (pinfunction "I/O_202") (pintype "bidirectional"))
    )
    (net (code "79") (name "/LA20") (class "Default")
      (node (ref "S3") (pin "C5") (pinfunction "C5_C5") (pintype "passive"))
      (node (ref "U11") (pin "203") (pinfunction "I/O_203") (pintype "bidirectional"))
    )
    (net (code "80") (name "/LA21") (class "Default")
      (node (ref "S3") (pin "C4") (pinfunction "C4_C4") (pintype "passive"))
      (node (ref "U11") (pin "204") (pinfunction "I/O_204") (pintype "bidirectional"))
    )
    (net (code "81") (name "/LA22") (class "Default")
      (node (ref "S3") (pin "C3") (pinfunction "C3_C3") (pintype "passive"))
      (node (ref "U11") (pin "205") (pinfunction "I/O_205") (pintype "bidirectional"))
    )
    (net (code "82") (name "/LA23") (class "Default")
      (node (ref "S3") (pin "C2") (pinfunction "C2_C2") (pintype "passive"))
      (node (ref "U11") (pin "206") (pinfunction "I/O_206") (pintype "bidirectional"))
    )
    (net (code "83") (name "/LED_KVR") (class "Default")
      (node (ref "R18") (pin "2") (pinfunction "2_2") (pintype "passive"))
      (node (ref "U11") (pin "131") (pinfunction "I/O_131") (pintype "bidirectional"))
    )
    (net (code "84") (name "/LED_LPT") (class "Default")
      (node (ref "R20") (pin "2") (pinfunction "2_2") (pintype "passive"))
      (node (ref "U11") (pin "132") (pinfunction "I/O_132") (pintype "bidirectional"))
    )
    (net (code "85") (name "/LED_MASTER_ENABLE") (class "Default")
      (node (ref "R21") (pin "2") (pinfunction "2_2") (pintype "passive"))
      (node (ref "U11") (pin "109") (pinfunction "I/O_109") (pintype "bidirectional"))
    )
    (net (code "86") (name "/LED_PWR_GOOD_TPS") (class "Default")
      (node (ref "R22") (pin "2") (pinfunction "2_2") (pintype "passive"))
      (node (ref "U11") (pin "118") (pinfunction "I/O_118") (pintype "bidirectional"))
    )
    (net (code "87") (name "/LED_RAD") (class "Default")
      (node (ref "R17") (pin "2") (pinfunction "2_2") (pintype "passive"))
      (node (ref "U11") (pin "130") (pinfunction "I/O_130") (pintype "bidirectional"))
    )
    (net (code "88") (name "/LED_WDT") (class "Default")
      (node (ref "R19") (pin "2") (pinfunction "2_2") (pintype "passive"))
      (node (ref "U11") (pin "117") (pinfunction "I/O_117") (pintype "bidirectional"))
    )
    (net (code "89") (name "/MASTER_ENABLE") (class "Default")
      (node (ref "U11") (pin "113") (pinfunction "I/O_113") (pintype "bidirectional"))
    )
    (net (code "90") (name "/MRST") (class "Default")
      (node (ref "U11") (pin "141") (pinfunction "I/O_141") (pintype "bidirectional"))
    )
    (net (code "91") (name "/MS_IN_1") (class "Default")
      (node (ref "U11") (pin "88") (pinfunction "I/O_88") (pintype "bidirectional"))
    )
    (net (code "92") (name "/NVRAM_ADDRESS0") (class "Default")
      (node (ref "U11") (pin "129") (pinfunction "I/O_129") (pintype "bidirectional"))
    )
    (net (code "93") (name "/NVRAM_ADDRESS1") (class "Default")
      (node (ref "U11") (pin "128") (pinfunction "I/O_128") (pintype "bidirectional"))
    )
    (net (code "94") (name "/NVRAM_ADDRESS2") (class "Default")
      (node (ref "U11") (pin "126") (pinfunction "I/O_126") (pintype "bidirectional"))
    )
    (net (code "95") (name "/NVRAM_ADDRESS3") (class "Default")
      (node (ref "U11") (pin "124") (pinfunction "I/O_124") (pintype "bidirectional"))
    )
    (net (code "96") (name "/NVRAM_ADDRESS4") (class "Default")
      (node (ref "U11") (pin "123") (pinfunction "I/O_123") (pintype "bidirectional"))
    )
    (net (code "97") (name "/NVRAM_ADDRESS5") (class "Default")
      (node (ref "U11") (pin "122") (pinfunction "I/O_122") (pintype "bidirectional"))
    )
    (net (code "98") (name "/NVRAM_ADDRESS6") (class "Default")
      (node (ref "U11") (pin "121") (pinfunction "I/O_121") (pintype "bidirectional"))
    )
    (net (code "99") (name "/NVRAM_ADDRESS7") (class "Default")
      (node (ref "U11") (pin "120") (pinfunction "I/O_120") (pintype "bidirectional"))
    )
    (net (code "100") (name "/NVRAM_ADDRESS8") (class "Default")
      (node (ref "U11") (pin "119") (pinfunction "I/O_119") (pintype "bidirectional"))
    )
    (net (code "101") (name "/NVRAM_ADDRESS9") (class "Default")
      (node (ref "U11") (pin "102") (pinfunction "I/O_102") (pintype "bidirectional"))
    )
    (net (code "102") (name "/NVRAM_ADDRESS10") (class "Default")
      (node (ref "U11") (pin "101") (pinfunction "I/O_101") (pintype "bidirectional"))
    )
    (net (code "103") (name "/NVRAM_ADDRESS11") (class "Default")
      (node (ref "U11") (pin "100") (pinfunction "I/O_100") (pintype "bidirectional"))
    )
    (net (code "104") (name "/NVRAM_ADDRESS12") (class "Default")
      (node (ref "U11") (pin "99") (pinfunction "I/O_99") (pintype "bidirectional"))
    )
    (net (code "105") (name "/NVRAM_ADDRESS13") (class "Default")
      (node (ref "U11") (pin "98") (pinfunction "I/O_98") (pintype "bidirectional"))
    )
    (net (code "106") (name "/NVRAM_ADDRESS14") (class "Default")
      (node (ref "U11") (pin "97") (pinfunction "I/O_97") (pintype "bidirectional"))
    )
    (net (code "107") (name "/NVRAM_ADDRESS15") (class "Default")
      (node (ref "U11") (pin "96") (pinfunction "I/O_96") (pintype "bidirectional"))
    )
    (net (code "108") (name "/NVRAM_ADDRESS16") (class "Default")
      (node (ref "U11") (pin "95") (pinfunction "I/O_95") (pintype "bidirectional"))
    )
    (net (code "109") (name "/NVRAM_ADDRESS17") (class "Default")
      (node (ref "U11") (pin "93") (pinfunction "I/O_93") (pintype "bidirectional"))
    )
    (net (code "110") (name "/NVRAM_ADDRESS18") (class "Default")
      (node (ref "U11") (pin "92") (pinfunction "I/O_92") (pintype "bidirectional"))
    )
    (net (code "111") (name "/NVRAM_ADDRESS19") (class "Default")
      (node (ref "U11") (pin "91") (pinfunction "I/O_91") (pintype "bidirectional"))
    )
    (net (code "112") (name "/NVRAM_ADDRESS20") (class "Default")
      (node (ref "U11") (pin "90") (pinfunction "I/O_90") (pintype "bidirectional"))
    )
    (net (code "113") (name "/NVRAM_CE") (class "Default")
      (node (ref "U11") (pin "133") (pinfunction "I/O_133") (pintype "bidirectional"))
    )
    (net (code "114") (name "/NVRAM_DATA0") (class "Default")
      (node (ref "U11") (pin "188") (pinfunction "I/O_188") (pintype "bidirectional"))
    )
    (net (code "115") (name "/NVRAM_DATA1") (class "Default")
      (node (ref "U11") (pin "190") (pinfunction "I/O_190") (pintype "bidirectional"))
    )
    (net (code "116") (name "/NVRAM_DATA2") (class "Default")
      (node (ref "U11") (pin "192") (pinfunction "I/O_192") (pintype "bidirectional"))
    )
    (net (code "117") (name "/NVRAM_DATA3") (class "Default")
      (node (ref "U11") (pin "193") (pinfunction "I/O_193") (pintype "bidirectional"))
    )
    (net (code "118") (name "/NVRAM_DATA4") (class "Default")
      (node (ref "U11") (pin "194") (pinfunction "I/O_194") (pintype "bidirectional"))
    )
    (net (code "119") (name "/NVRAM_DATA5") (class "Default")
      (node (ref "U11") (pin "195") (pinfunction "I/O_195") (pintype "bidirectional"))
    )
    (net (code "120") (name "/NVRAM_DATA6") (class "Default")
      (node (ref "U11") (pin "196") (pinfunction "I/O_196") (pintype "bidirectional"))
    )
    (net (code "121") (name "/NVRAM_DATA7") (class "Default")
      (node (ref "U11") (pin "197") (pinfunction "I/O_197") (pintype "bidirectional"))
    )
    (net (code "122") (name "/NVRAM_OE") (class "Default")
      (node (ref "U11") (pin "136") (pinfunction "I/O_136") (pintype "bidirectional"))
    )
    (net (code "123") (name "/NVRAM_RST") (class "Default")
      (node (ref "U11") (pin "178") (pinfunction "I/O_178") (pintype "bidirectional"))
    )
    (net (code "124") (name "/NVRAM_WE") (class "Default")
      (node (ref "U11") (pin "137") (pinfunction "I/O_137") (pintype "bidirectional"))
    )
    (net (code "125") (name "/PPM_NOVI") (class "Default")
      (node (ref "U11") (pin "57") (pinfunction "I/O_57") (pintype "bidirectional"))
    )
    (net (code "126") (name "/PWR_GOOD_TPS") (class "Default")
      (node (ref "U11") (pin "149") (pinfunction "I/O_149") (pintype "bidirectional"))
    )
    (net (code "127") (name "/RESERVE1") (class "Default")
      (node (ref "U11") (pin "114") (pinfunction "I/O_114") (pintype "bidirectional"))
    )
    (net (code "128") (name "/RESERVE2") (class "Default")
      (node (ref "U11") (pin "115") (pinfunction "I/O_115") (pintype "bidirectional"))
    )
    (net (code "129") (name "/RESET_CPU") (class "Default")
      (node (ref "U11") (pin "111") (pinfunction "I/O_111") (pintype "bidirectional"))
    )
    (net (code "130") (name "/RES_DRV") (class "Default")
      (node (ref "S3") (pin "B2") (pinfunction "B2_B2") (pintype "passive"))
      (node (ref "U11") (pin "144") (pinfunction "I/O_144") (pintype "bidirectional"))
    )
    (net (code "131") (name "/RST_DOF_EN") (class "Default")
      (node (ref "J18") (pin "1") (pinfunction "1_1") (pintype "passive"))
      (node (ref "R30") (pin "1") (pinfunction "1_1") (pintype "passive"))
      (node (ref "S3") (pin "A28") (pinfunction "A28_A28") (pintype "passive"))
      (node (ref "U11") (pin "173") (pinfunction "I/O_173") (pintype "bidirectional"))
      (node (ref "U11") (pin "7") (pinfunction "I/O_7") (pintype "bidirectional"))
    )
    (net (code "132") (name "/SA0") (class "Default")
      (node (ref "S3") (pin "A31") (pinfunction "A31_A31") (pintype "passive"))
      (node (ref "U11") (pin "3") (pinfunction "I/O_3") (pintype "bidirectional"))
    )
    (net (code "133") (name "/SA1") (class "Default")
      (node (ref "S3") (pin "A30") (pinfunction "A30_A30") (pintype "passive"))
      (node (ref "U11") (pin "4") (pinfunction "I/O_4") (pintype "bidirectional"))
    )
    (net (code "134") (name "/SA2") (class "Default")
      (node (ref "S3") (pin "A29") (pinfunction "A29_A29") (pintype "passive"))
      (node (ref "U11") (pin "6") (pinfunction "I/O_6") (pintype "bidirectional"))
    )
    (net (code "135") (name "/SA4") (class "Default")
      (node (ref "S3") (pin "A27") (pinfunction "A27_A27") (pintype "passive"))
      (node (ref "U11") (pin "8") (pinfunction "I/O_8") (pintype "bidirectional"))
    )
    (net (code "136") (name "/SA5") (class "Default")
      (node (ref "S3") (pin "A26") (pinfunction "A26_A26") (pintype "passive"))
      (node (ref "U11") (pin "9") (pinfunction "I/O_9") (pintype "bidirectional"))
    )
    (net (code "137") (name "/SA6") (class "Default")
      (node (ref "S3") (pin "A25") (pinfunction "A25_A25") (pintype "passive"))
      (node (ref "U11") (pin "10") (pinfunction "I/O_10") (pintype "bidirectional"))
    )
    (net (code "138") (name "/SA7") (class "Default")
      (node (ref "S3") (pin "A24") (pinfunction "A24_A24") (pintype "passive"))
      (node (ref "U11") (pin "11") (pinfunction "I/O_11") (pintype "bidirectional"))
    )
    (net (code "139") (name "/SA8") (class "Default")
      (node (ref "S3") (pin "A23") (pinfunction "A23_A23") (pintype "passive"))
      (node (ref "U11") (pin "12") (pinfunction "I/O_12") (pintype "bidirectional"))
    )
    (net (code "140") (name "/SA9") (class "Default")
      (node (ref "S3") (pin "A22") (pinfunction "A22_A22") (pintype "passive"))
      (node (ref "U11") (pin "13") (pinfunction "I/O_13") (pintype "bidirectional"))
    )
    (net (code "141") (name "/SA10") (class "Default")
      (node (ref "S3") (pin "A21") (pinfunction "A21_A21") (pintype "passive"))
      (node (ref "U11") (pin "15") (pinfunction "I/O_15") (pintype "bidirectional"))
    )
    (net (code "142") (name "/SA11") (class "Default")
      (node (ref "S3") (pin "A20") (pinfunction "A20_A20") (pintype "passive"))
      (node (ref "U11") (pin "16") (pinfunction "I/O_16") (pintype "bidirectional"))
    )
    (net (code "143") (name "/SA12") (class "Default")
      (node (ref "S3") (pin "A19") (pinfunction "A19_A19") (pintype "passive"))
      (node (ref "U11") (pin "17") (pinfunction "I/O_17") (pintype "bidirectional"))
    )
    (net (code "144") (name "/SA13") (class "Default")
      (node (ref "S3") (pin "A18") (pinfunction "A18_A18") (pintype "passive"))
      (node (ref "U11") (pin "18") (pinfunction "I/O_18") (pintype "bidirectional"))
    )
    (net (code "145") (name "/SA14") (class "Default")
      (node (ref "S3") (pin "A17") (pinfunction "A17_A17") (pintype "passive"))
      (node (ref "U11") (pin "19") (pinfunction "I/O_19") (pintype "bidirectional"))
    )
    (net (code "146") (name "/SA15") (class "Default")
      (node (ref "S3") (pin "A16") (pinfunction "A16_A16") (pintype "passive"))
      (node (ref "U11") (pin "20") (pinfunction "I/O_20") (pintype "bidirectional"))
    )
    (net (code "147") (name "/SA16") (class "Default")
      (node (ref "S3") (pin "A15") (pinfunction "A15_A15") (pintype "passive"))
      (node (ref "U11") (pin "198") (pinfunction "I/O_198") (pintype "bidirectional"))
    )
    (net (code "148") (name "/SBHE") (class "Default")
      (node (ref "S3") (pin "C1") (pinfunction "C1_C1") (pintype "passive"))
      (node (ref "U11") (pin "187") (pinfunction "I/O_187") (pintype "bidirectional"))
    )
    (net (code "149") (name "/SMEMR") (class "Default")
      (node (ref "S3") (pin "B12") (pinfunction "B12_B12") (pintype "passive"))
      (node (ref "U11") (pin "138") (pinfunction "I/O_138") (pintype "bidirectional"))
    )
    (net (code "150") (name "/SMEMW") (class "Default")
      (node (ref "S3") (pin "B11") (pinfunction "B11_B11") (pintype "passive"))
      (node (ref "U11") (pin "139") (pinfunction "I/O_139") (pintype "bidirectional"))
    )
    (net (code "151") (name "/TCK") (class "Default")
      (node (ref "J14") (pin "6") (pinfunction "6_6") (pintype "passive"))
      (node (ref "RN12") (pin "6") (pinfunction "6_6") (pintype "passive"))
      (node (ref "U11") (pin "30") (pinfunction "TCK_30") (pintype "passive"))
    )
    (net (code "152") (name "/TDI") (class "Default")
      (node (ref "J14") (pin "10") (pinfunction "10_10") (pintype "passive"))
      (node (ref "RN12") (pin "8") (pinfunction "8_8") (pintype "passive"))
      (node (ref "U11") (pin "176") (pinfunction "TDI_176") (pintype "passive"))
    )
    (net (code "153") (name "/TDO") (class "Default")
      (node (ref "J14") (pin "8") (pinfunction "8_8") (pintype "passive"))
      (node (ref "RN12") (pin "7") (pinfunction "7_7") (pintype "passive"))
      (node (ref "U11") (pin "189") (pinfunction "TDO_189") (pintype "tri_state"))
    )
    (net (code "154") (name "/TMS") (class "Default")
      (node (ref "J14") (pin "4") (pinfunction "4_4") (pintype "passive"))
      (node (ref "RN12") (pin "5") (pinfunction "5_5") (pintype "passive"))
      (node (ref "U11") (pin "127") (pinfunction "TMS_127") (pintype "passive"))
    )
    (net (code "155") (name "/VCC_+12V") (class "Default")
      (node (ref "U13") (pin "8") (pinfunction "A8_8") (pintype "passive"))
    )
    (net (code "156") (name "/VCC_-12V") (class "Default")
      (node (ref "R24") (pin "2") (pinfunction "2_2") (pintype "passive"))
    )
    (net (code "157") (name "/WDT_OUT_STARI") (class "Default")
      (node (ref "U11") (pin "56") (pinfunction "I/O_56") (pintype "bidirectional"))
    )
    (net (code "158") (name "/WDT_SIG_STARI") (class "Default")
      (node (ref "U11") (pin "68") (pinfunction "I/O_68") (pintype "bidirectional"))
    )
    (net (code "159") (name "/WDT_TRG") (class "Default")
      (node (ref "U11") (pin "55") (pinfunction "I/O_55") (pintype "bidirectional"))
    )
    (net (code "160") (name "/XP_PRESENT_IN") (class "Default")
      (node (ref "RN10") (pin "5") (pinfunction "5_5") (pintype "passive"))
      (node (ref "U11") (pin "89") (pinfunction "I/O_89") (pintype "bidirectional"))
    )
    (net (code "161") (name "/XP_PRESENT_OUT") (class "Default")
      (node (ref "S2") (pin "8") (pinfunction "A8_8") (pintype "passive"))
    )
    (net (code "162") (name "/{slash}FLTB1") (class "Default")
      (node (ref "U11") (pin "58") (pinfunction "I/O_58") (pintype "bidirectional"))
    )
    (net (code "163") (name "/{slash}NVRAM_RST") (class "Default")
      (node (ref "U11") (pin "140") (pinfunction "I/O_140") (pintype "bidirectional"))
    )
    (net (code "164") (name "GND") (class "Default")
      (node (ref "C14") (pin "2") (pinfunction "2_2") (pintype "passive"))
      (node (ref "C15") (pin "2") (pinfunction "2_2") (pintype "passive"))
      (node (ref "C16") (pin "2") (pinfunction "2_2") (pintype "passive"))
      (node (ref "C17") (pin "2") (pinfunction "2_2") (pintype "passive"))
      (node (ref "C18") (pin "2") (pinfunction "2_2") (pintype "passive"))
      (node (ref "C19") (pin "2") (pinfunction "2_2") (pintype "passive"))
      (node (ref "C20") (pin "2") (pinfunction "2_2") (pintype "passive"))
      (node (ref "C21") (pin "2") (pinfunction "2_2") (pintype "passive"))
      (node (ref "C22") (pin "2") (pinfunction "2_2") (pintype "passive"))
      (node (ref "C23") (pin "2") (pinfunction "2_2") (pintype "passive"))
      (node (ref "C24") (pin "2") (pinfunction "2_2") (pintype "passive"))
      (node (ref "C25") (pin "2") (pinfunction "2_2") (pintype "passive"))
      (node (ref "C26") (pin "2") (pinfunction "2_2") (pintype "passive"))
      (node (ref "C27") (pin "2") (pinfunction "2_2") (pintype "passive"))
      (node (ref "C28") (pin "2") (pinfunction "2_2") (pintype "passive"))
      (node (ref "C29") (pin "2") (pinfunction "2_2") (pintype "passive"))
      (node (ref "C30") (pin "2") (pinfunction "2_2") (pintype "passive"))
      (node (ref "C31") (pin "2") (pinfunction "2_2") (pintype "passive"))
      (node (ref "C32") (pin "2") (pinfunction "2_2") (pintype "passive"))
      (node (ref "C33") (pin "2") (pinfunction "2_2") (pintype "passive"))
      (node (ref "C34") (pin "2") (pinfunction "2_2") (pintype "passive"))
      (node (ref "C35") (pin "2") (pinfunction "2_2") (pintype "passive"))
      (node (ref "C36") (pin "2") (pinfunction "2_2") (pintype "passive"))
      (node (ref "C37") (pin "2") (pinfunction "2_2") (pintype "passive"))
      (node (ref "C38") (pin "2") (pinfunction "2_2") (pintype "passive"))
      (node (ref "C39") (pin "2") (pinfunction "2_2") (pintype "passive"))
      (node (ref "C40") (pin "2") (pinfunction "2_2") (pintype "passive"))
      (node (ref "C41") (pin "2") (pinfunction "2_2") (pintype "passive"))
      (node (ref "C42") (pin "2") (pinfunction "2_2") (pintype "passive"))
      (node (ref "C47") (pin "2") (pinfunction "2_2") (pintype "passive"))
      (node (ref "C48") (pin "2") (pinfunction "2_2") (pintype "passive"))
      (node (ref "C50") (pin "2") (pinfunction "2_2") (pintype "passive"))
      (node (ref "J11") (pin "2") (pinfunction "2_2") (pintype "passive"))
      (node (ref "J13") (pin "2") (pinfunction "2_2") (pintype "passive"))
      (node (ref "J14") (pin "1") (pinfunction "1_1") (pintype "passive"))
      (node (ref "J14") (pin "11") (pinfunction "11_11") (pintype "passive"))
      (node (ref "J14") (pin "13") (pinfunction "13_13") (pintype "passive"))
      (node (ref "J14") (pin "3") (pinfunction "3_3") (pintype "passive"))
      (node (ref "J14") (pin "5") (pinfunction "5_5") (pintype "passive"))
      (node (ref "J14") (pin "7") (pinfunction "7_7") (pintype "passive"))
      (node (ref "J14") (pin "9") (pinfunction "9_9") (pintype "passive"))
      (node (ref "J18") (pin "2") (pinfunction "2_2") (pintype "passive"))
      (node (ref "R23") (pin "2") (pinfunction "2_2") (pintype "passive"))
      (node (ref "S2") (pin "10") (pinfunction "B7_10") (pintype "passive"))
      (node (ref "S2") (pin "11") (pinfunction "B6_11") (pintype "passive"))
      (node (ref "S2") (pin "12") (pinfunction "B5_12") (pintype "passive"))
      (node (ref "S2") (pin "13") (pinfunction "B4_13") (pintype "passive"))
      (node (ref "S2") (pin "14") (pinfunction "B3_14") (pintype "passive"))
      (node (ref "S2") (pin "15") (pinfunction "B2_15") (pintype "passive"))
      (node (ref "S2") (pin "16") (pinfunction "B1_16") (pintype "passive"))
      (node (ref "S2") (pin "9") (pinfunction "B8_9") (pintype "passive"))
      (node (ref "S3") (pin "A32") (pinfunction "A32_A32") (pintype "passive"))
      (node (ref "S3") (pin "B1") (pinfunction "B1_B1") (pintype "passive"))
      (node (ref "S3") (pin "B10") (pinfunction "B10_B10") (pintype "passive"))
      (node (ref "S3") (pin "B31") (pinfunction "B31_B31") (pintype "passive"))
      (node (ref "S3") (pin "B32") (pinfunction "B32_B32") (pintype "passive"))
      (node (ref "S3") (pin "C0") (pinfunction "C0_C0") (pintype "passive"))
      (node (ref "S3") (pin "C19") (pinfunction "C19_C19") (pintype "passive"))
      (node (ref "S3") (pin "D0") (pinfunction "D0_D0") (pintype "passive"))
      (node (ref "S3") (pin "D18") (pinfunction "D18_D18") (pintype "passive"))
      (node (ref "S3") (pin "D19") (pinfunction "D19_D19") (pintype "passive"))
      (node (ref "S3") (pin "MTH1") (pinfunction "MTH1_MTH1") (pintype "passive"))
      (node (ref "S3") (pin "MTH2") (pinfunction "MTH2_MTH2") (pintype "passive"))
      (node (ref "S3") (pin "MTH3") (pinfunction "MTH3_MTH3") (pintype "passive"))
      (node (ref "S3") (pin "MTH4") (pinfunction "MTH4_MTH4") (pintype "passive"))
      (node (ref "S3") (pin "MTH5") (pinfunction "MTH5_MTH5") (pintype "passive"))
      (node (ref "S3") (pin "MTH7") (pinfunction "MTH7_MTH7") (pintype "passive"))
      (node (ref "STB1") (pin "2") (pinfunction "GND_2") (pintype "power_in"))
      (node (ref "STB1") (pin "4") (pinfunction "GND_4") (pintype "power_in"))
      (node (ref "U11") (pin "116") (pinfunction "PORT_EN_116") (pintype "passive"))
      (node (ref "U11") (pin "134") (pinfunction "GND_134") (pintype "power_in"))
      (node (ref "U11") (pin "14") (pinfunction "GND_14") (pintype "power_in"))
      (node (ref "U11") (pin "152") (pinfunction "GND_152") (pintype "power_in"))
      (node (ref "U11") (pin "174") (pinfunction "GND_174") (pintype "power_in"))
      (node (ref "U11") (pin "180") (pinfunction "GND_180") (pintype "power_in"))
      (node (ref "U11") (pin "185") (pinfunction "GND_185") (pintype "power_in"))
      (node (ref "U11") (pin "200") (pinfunction "GND_200") (pintype "power_in"))
      (node (ref "U11") (pin "32") (pinfunction "GND_32") (pintype "power_in"))
      (node (ref "U11") (pin "50") (pinfunction "GND_50") (pintype "power_in"))
      (node (ref "U11") (pin "72") (pinfunction "GND_72") (pintype "power_in"))
      (node (ref "U11") (pin "75") (pinfunction "GND_75") (pintype "power_in"))
      (node (ref "U11") (pin "82") (pinfunction "GND_82") (pintype "power_in"))
      (node (ref "U11") (pin "94") (pinfunction "GND_94") (pintype "power_in"))
      (node (ref "U12") (pin "2") (pinfunction "GND_2") (pintype "power_in"))
      (node (ref "U13") (pin "10") (pinfunction "K2_10") (pintype "passive"))
      (node (ref "U13") (pin "11") (pinfunction "K3_11") (pintype "passive"))
      (node (ref "U13") (pin "12") (pinfunction "K4_12") (pintype "passive"))
      (node (ref "U13") (pin "13") (pinfunction "K5_13") (pintype "passive"))
      (node (ref "U13") (pin "14") (pinfunction "K6_14") (pintype "passive"))
      (node (ref "U13") (pin "9") (pinfunction "K1_9") (pintype "passive"))
      (node (ref "U4") (pin "1") (pinfunction "1_1") (pintype "passive"))
    )
    (net (code "165") (name "Net-(U13-A1)") (class "Default")
      (node (ref "R17") (pin "1") (pinfunction "1_1") (pintype "passive"))
      (node (ref "U13") (pin "1") (pinfunction "A1_1") (pintype "passive"))
    )
    (net (code "166") (name "Net-(U13-A2)") (class "Default")
      (node (ref "R18") (pin "1") (pinfunction "1_1") (pintype "passive"))
      (node (ref "U13") (pin "2") (pinfunction "A2_2") (pintype "passive"))
    )
    (net (code "167") (name "Net-(U13-A3)") (class "Default")
      (node (ref "R19") (pin "1") (pinfunction "1_1") (pintype "passive"))
      (node (ref "U13") (pin "3") (pinfunction "A3_3") (pintype "passive"))
    )
    (net (code "168") (name "Net-(U13-A4)") (class "Default")
      (node (ref "R20") (pin "1") (pinfunction "1_1") (pintype "passive"))
      (node (ref "U13") (pin "4") (pinfunction "A4_4") (pintype "passive"))
    )
    (net (code "169") (name "Net-(U13-A5)") (class "Default")
      (node (ref "R21") (pin "1") (pinfunction "1_1") (pintype "passive"))
      (node (ref "U13") (pin "5") (pinfunction "A5_5") (pintype "passive"))
    )
    (net (code "170") (name "Net-(U13-A6)") (class "Default")
      (node (ref "R22") (pin "1") (pinfunction "1_1") (pintype "passive"))
      (node (ref "U13") (pin "6") (pinfunction "A6_6") (pintype "passive"))
    )
    (net (code "171") (name "Net-(U13-K7)") (class "Default")
      (node (ref "R23") (pin "1") (pinfunction "1_1") (pintype "passive"))
      (node (ref "U13") (pin "15") (pinfunction "K7_15") (pintype "passive"))
    )
    (net (code "172") (name "Net-(U13-K8)") (class "Default")
      (node (ref "R24") (pin "1") (pinfunction "1_1") (pintype "passive"))
      (node (ref "U13") (pin "16") (pinfunction "K8_16") (pintype "passive"))
    )
    (net (code "173") (name "VCC_+5V") (class "Default")
      (node (ref "C42") (pin "1") (pinfunction "1_1") (pintype "passive"))
      (node (ref "D4") (pin "2") (pinfunction "CATHODE_2") (pintype "passive"))
      (node (ref "S3") (pin "B29") (pinfunction "B29_B29") (pintype "passive"))
      (node (ref "S3") (pin "B3") (pinfunction "B3_B3") (pintype "passive"))
      (node (ref "S3") (pin "D16") (pinfunction "D16_D16") (pintype "passive"))
      (node (ref "STB1") (pin "1") (pinfunction "IN_1") (pintype "power_in"))
      (node (ref "U13") (pin "7") (pinfunction "A7_7") (pintype "passive"))
      (node (ref "UR3") (pin "1") (pinfunction "1_1") (pintype "power_in"))
      (node (ref "UR4") (pin "1") (pinfunction "1_1") (pintype "power_in"))
    )
    (net (code "174") (name "VCC_3V3") (class "Default")
      (node (ref "C14") (pin "1") (pinfunction "1_1") (pintype "passive"))
      (node (ref "C15") (pin "1") (pinfunction "1_1") (pintype "passive"))
      (node (ref "C16") (pin "1") (pinfunction "1_1") (pintype "passive"))
      (node (ref "C17") (pin "1") (pinfunction "1_1") (pintype "passive"))
      (node (ref "C18") (pin "1") (pinfunction "1_1") (pintype "passive"))
      (node (ref "C19") (pin "1") (pinfunction "1_1") (pintype "passive"))
      (node (ref "C20") (pin "1") (pinfunction "1_1") (pintype "passive"))
      (node (ref "C21") (pin "1") (pinfunction "1_1") (pintype "passive"))
      (node (ref "C22") (pin "1") (pinfunction "1_1") (pintype "passive"))
      (node (ref "C23") (pin "1") (pinfunction "1_1") (pintype "passive"))
      (node (ref "C24") (pin "1") (pinfunction "1_1") (pintype "passive"))
      (node (ref "C25") (pin "1") (pinfunction "1_1") (pintype "passive"))
      (node (ref "C26") (pin "1") (pinfunction "1_1") (pintype "passive"))
      (node (ref "C27") (pin "1") (pinfunction "1_1") (pintype "passive"))
      (node (ref "C28") (pin "1") (pinfunction "1_1") (pintype "passive"))
      (node (ref "C29") (pin "1") (pinfunction "1_1") (pintype "passive"))
      (node (ref "C30") (pin "1") (pinfunction "1_1") (pintype "passive"))
      (node (ref "C31") (pin "1") (pinfunction "1_1") (pintype "passive"))
      (node (ref "C32") (pin "1") (pinfunction "1_1") (pintype "passive"))
      (node (ref "C33") (pin "1") (pinfunction "1_1") (pintype "passive"))
      (node (ref "C34") (pin "1") (pinfunction "1_1") (pintype "passive"))
      (node (ref "C35") (pin "1") (pinfunction "1_1") (pintype "passive"))
      (node (ref "C36") (pin "1") (pinfunction "1_1") (pintype "passive"))
      (node (ref "C37") (pin "1") (pinfunction "1_1") (pintype "passive"))
      (node (ref "C38") (pin "1") (pinfunction "1_1") (pintype "passive"))
      (node (ref "C39") (pin "1") (pinfunction "1_1") (pintype "passive"))
      (node (ref "C40") (pin "1") (pinfunction "1_1") (pintype "passive"))
      (node (ref "C41") (pin "1") (pinfunction "1_1") (pintype "passive"))
      (node (ref "C47") (pin "1") (pinfunction "1_1") (pintype "passive"))
      (node (ref "C48") (pin "1") (pinfunction "1_1") (pintype "passive"))
      (node (ref "C50") (pin "1") (pinfunction "1_1") (pintype "passive"))
      (node (ref "D4") (pin "1") (pinfunction "ANODE_1") (pintype "passive"))
      (node (ref "J14") (pin "2") (pinfunction "2_2") (pintype "passive"))
      (node (ref "R30") (pin "2") (pinfunction "2_2") (pintype "passive"))
      (node (ref "RN10") (pin "1") (pinfunction "1_1") (pintype "passive"))
      (node (ref "RN10") (pin "2") (pinfunction "2_2") (pintype "passive"))
      (node (ref "RN10") (pin "3") (pinfunction "3_3") (pintype "passive"))
      (node (ref "RN10") (pin "4") (pinfunction "4_4") (pintype "passive"))
      (node (ref "RN11") (pin "1") (pinfunction "1_1") (pintype "passive"))
      (node (ref "RN11") (pin "2") (pinfunction "2_2") (pintype "passive"))
      (node (ref "RN11") (pin "3") (pinfunction "3_3") (pintype "passive"))
      (node (ref "RN11") (pin "4") (pinfunction "4_4") (pintype "passive"))
      (node (ref "RN12") (pin "1") (pinfunction "1_1") (pintype "passive"))
      (node (ref "RN12") (pin "2") (pinfunction "2_2") (pintype "passive"))
      (node (ref "RN12") (pin "3") (pinfunction "3_3") (pintype "passive"))
      (node (ref "RN12") (pin "4") (pinfunction "4_4") (pintype "passive"))
      (node (ref "RN13") (pin "1") (pinfunction "1_1") (pintype "passive"))
      (node (ref "RN13") (pin "2") (pinfunction "2_2") (pintype "passive"))
      (node (ref "RN13") (pin "3") (pinfunction "3_3") (pintype "passive"))
      (node (ref "RN13") (pin "4") (pinfunction "4_4") (pintype "passive"))
      (node (ref "RN14") (pin "1") (pinfunction "1_1") (pintype "passive"))
      (node (ref "RN14") (pin "2") (pinfunction "2_2") (pintype "passive"))
      (node (ref "RN14") (pin "3") (pinfunction "3_3") (pintype "passive"))
      (node (ref "RN14") (pin "4") (pinfunction "4_4") (pintype "passive"))
      (node (ref "STB1") (pin "3") (pinfunction "OUT_3") (pintype "power_in"))
      (node (ref "U11") (pin "107") (pinfunction "VCC_107") (pintype "power_in"))
      (node (ref "U11") (pin "125") (pinfunction "VCC_125") (pintype "power_in"))
      (node (ref "U11") (pin "143") (pinfunction "VCC_143") (pintype "power_in"))
      (node (ref "U11") (pin "165") (pinfunction "VCC_165") (pintype "power_in"))
      (node (ref "U11") (pin "179") (pinfunction "VCC_179") (pintype "power_in"))
      (node (ref "U11") (pin "186") (pinfunction "VCC_186") (pintype "power_in"))
      (node (ref "U11") (pin "191") (pinfunction "VCC_191") (pintype "power_in"))
      (node (ref "U11") (pin "23") (pinfunction "VCC_23") (pintype "power_in"))
      (node (ref "U11") (pin "41") (pinfunction "VCC_41") (pintype "power_in"))
      (node (ref "U11") (pin "5") (pinfunction "VCC_5") (pintype "power_in"))
      (node (ref "U11") (pin "63") (pinfunction "VCC_63") (pintype "power_in"))
      (node (ref "U11") (pin "74") (pinfunction "VCC_74") (pintype "power_in"))
      (node (ref "U11") (pin "83") (pinfunction "VCC_83") (pintype "power_in"))
      (node (ref "U11") (pin "85") (pinfunction "VCC_85") (pintype "power_in"))
      (node (ref "U12") (pin "4") (pinfunction "VDD_4") (pintype "power_in"))
      (node (ref "UR1") (pin "1") (pinfunction "1_1") (pintype "power_in"))
      (node (ref "UR2") (pin "1") (pinfunction "1_1") (pintype "power_in"))
    )
    (net (code "175") (name "unconnected-(J14-Pad12)") (class "Default")
      (node (ref "J14") (pin "12") (pinfunction "12_12") (pintype "passive"))
    )
    (net (code "176") (name "unconnected-(J14-Pad14)") (class "Default")
      (node (ref "J14") (pin "14") (pinfunction "14_14") (pintype "passive"))
    )
    (net (code "177") (name "unconnected-(J14-Pad15)") (class "Default")
      (node (ref "J14") (pin "15") (pinfunction "15_15") (pintype "passive"))
    )
    (net (code "178") (name "unconnected-(J14-Pad16)") (class "Default")
      (node (ref "J14") (pin "16") (pinfunction "16_16") (pintype "passive"))
    )
    (net (code "179") (name "unconnected-(RN10-Pad6)") (class "Default")
      (node (ref "RN10") (pin "6") (pinfunction "6_6") (pintype "passive"))
    )
    (net (code "180") (name "unconnected-(RN13-Pad8)") (class "Default")
      (node (ref "RN13") (pin "8") (pinfunction "8_8") (pintype "passive"))
    )
    (net (code "181") (name "unconnected-(RN14-Pad8)") (class "Default")
      (node (ref "RN14") (pin "8") (pinfunction "8_8") (pintype "passive"))
    )
    (net (code "182") (name "unconnected-(S2-A7-Pad7)") (class "Default")
      (node (ref "S2") (pin "7") (pinfunction "A7_7") (pintype "passive"))
    )
    (net (code "183") (name "unconnected-(S3-PadA1)") (class "Default")
      (node (ref "S3") (pin "A1") (pinfunction "A1_A1") (pintype "passive"))
    )
    (net (code "184") (name "unconnected-(S3-PadA10)") (class "Default")
      (node (ref "S3") (pin "A10") (pinfunction "A10_A10") (pintype "passive"))
    )
    (net (code "185") (name "unconnected-(S3-PadB5)") (class "Default")
      (node (ref "S3") (pin "B5") (pinfunction "B5_B5") (pintype "passive"))
    )
    (net (code "186") (name "unconnected-(S3-PadB6)") (class "Default")
      (node (ref "S3") (pin "B6") (pinfunction "B6_B6") (pintype "passive"))
    )
    (net (code "187") (name "unconnected-(S3-PadB7)") (class "Default")
      (node (ref "S3") (pin "B7") (pinfunction "B7_B7") (pintype "passive"))
    )
    (net (code "188") (name "unconnected-(S3-PadB8)") (class "Default")
      (node (ref "S3") (pin "B8") (pinfunction "B8_B8") (pintype "passive"))
    )
    (net (code "189") (name "unconnected-(S3-PadB9)") (class "Default")
      (node (ref "S3") (pin "B9") (pinfunction "B9_B9") (pintype "passive"))
    )
    (net (code "190") (name "unconnected-(S3-PadB15)") (class "Default")
      (node (ref "S3") (pin "B15") (pinfunction "B15_B15") (pintype "passive"))
    )
    (net (code "191") (name "unconnected-(S3-PadB16)") (class "Default")
      (node (ref "S3") (pin "B16") (pinfunction "B16_B16") (pintype "passive"))
    )
    (net (code "192") (name "unconnected-(S3-PadB17)") (class "Default")
      (node (ref "S3") (pin "B17") (pinfunction "B17_B17") (pintype "passive"))
    )
    (net (code "193") (name "unconnected-(S3-PadB18)") (class "Default")
      (node (ref "S3") (pin "B18") (pinfunction "B18_B18") (pintype "passive"))
    )
    (net (code "194") (name "unconnected-(S3-PadB19)") (class "Default")
      (node (ref "S3") (pin "B19") (pinfunction "B19_B19") (pintype "passive"))
    )
    (net (code "195") (name "unconnected-(S3-PadB20)") (class "Default")
      (node (ref "S3") (pin "B20") (pinfunction "B20_B20") (pintype "passive"))
    )
    (net (code "196") (name "unconnected-(S3-PadB21)") (class "Default")
      (node (ref "S3") (pin "B21") (pinfunction "B21_B21") (pintype "passive"))
    )
    (net (code "197") (name "unconnected-(S3-PadB22)") (class "Default")
      (node (ref "S3") (pin "B22") (pinfunction "B22_B22") (pintype "passive"))
    )
    (net (code "198") (name "unconnected-(S3-PadB23)") (class "Default")
      (node (ref "S3") (pin "B23") (pinfunction "B23_B23") (pintype "passive"))
    )
    (net (code "199") (name "unconnected-(S3-PadB24)") (class "Default")
      (node (ref "S3") (pin "B24") (pinfunction "B24_B24") (pintype "passive"))
    )
    (net (code "200") (name "unconnected-(S3-PadB25)") (class "Default")
      (node (ref "S3") (pin "B25") (pinfunction "B25_B25") (pintype "passive"))
    )
    (net (code "201") (name "unconnected-(S3-PadB26)") (class "Default")
      (node (ref "S3") (pin "B26") (pinfunction "B26_B26") (pintype "passive"))
    )
    (net (code "202") (name "unconnected-(S3-PadB27)") (class "Default")
      (node (ref "S3") (pin "B27") (pinfunction "B27_B27") (pintype "passive"))
    )
    (net (code "203") (name "unconnected-(S3-PadB30)") (class "Default")
      (node (ref "S3") (pin "B30") (pinfunction "B30_B30") (pintype "passive"))
    )
    (net (code "204") (name "unconnected-(S3-PadC6)") (class "Default")
      (node (ref "S3") (pin "C6") (pinfunction "C6_C6") (pintype "passive"))
    )
    (net (code "205") (name "unconnected-(S3-PadC7)") (class "Default")
      (node (ref "S3") (pin "C7") (pinfunction "C7_C7") (pintype "passive"))
    )
    (net (code "206") (name "unconnected-(S3-PadC8)") (class "Default")
      (node (ref "S3") (pin "C8") (pinfunction "C8_C8") (pintype "passive"))
    )
    (net (code "207") (name "unconnected-(S3-PadC9)") (class "Default")
      (node (ref "S3") (pin "C9") (pinfunction "C9_C9") (pintype "passive"))
    )
    (net (code "208") (name "unconnected-(S3-PadC10)") (class "Default")
      (node (ref "S3") (pin "C10") (pinfunction "C10_C10") (pintype "passive"))
    )
    (net (code "209") (name "unconnected-(S3-PadD1)") (class "Default")
      (node (ref "S3") (pin "D1") (pinfunction "D1_D1") (pintype "passive"))
    )
    (net (code "210") (name "unconnected-(S3-PadD8)") (class "Default")
      (node (ref "S3") (pin "D8") (pinfunction "D8_D8") (pintype "passive"))
    )
    (net (code "211") (name "unconnected-(S3-PadD9)") (class "Default")
      (node (ref "S3") (pin "D9") (pinfunction "D9_D9") (pintype "passive"))
    )
    (net (code "212") (name "unconnected-(S3-PadD10)") (class "Default")
      (node (ref "S3") (pin "D10") (pinfunction "D10_D10") (pintype "passive"))
    )
    (net (code "213") (name "unconnected-(S3-PadD11)") (class "Default")
      (node (ref "S3") (pin "D11") (pinfunction "D11_D11") (pintype "passive"))
    )
    (net (code "214") (name "unconnected-(S3-PadD12)") (class "Default")
      (node (ref "S3") (pin "D12") (pinfunction "D12_D12") (pintype "passive"))
    )
    (net (code "215") (name "unconnected-(S3-PadD13)") (class "Default")
      (node (ref "S3") (pin "D13") (pinfunction "D13_D13") (pintype "passive"))
    )
    (net (code "216") (name "unconnected-(S3-PadD14)") (class "Default")
      (node (ref "S3") (pin "D14") (pinfunction "D14_D14") (pintype "passive"))
    )
    (net (code "217") (name "unconnected-(S3-PadD15)") (class "Default")
      (node (ref "S3") (pin "D15") (pinfunction "D15_D15") (pintype "passive"))
    )
    (net (code "218") (name "unconnected-(S3-PadD17)") (class "Default")
      (node (ref "S3") (pin "D17") (pinfunction "D17_D17") (pintype "passive"))
    )
    (net (code "219") (name "unconnected-(S3-PadMTH6)") (class "Default")
      (node (ref "S3") (pin "MTH6") (pinfunction "MTH6_MTH6") (pintype "passive"))
    )
    (net (code "220") (name "unconnected-(U5-Pad1)") (class "Default")
      (node (ref "U5") (pin "1") (pinfunction "1_1") (pintype "passive"))
    )
    (net (code "221") (name "unconnected-(U11-I{slash}O-Pad24)") (class "Default")
      (node (ref "U11") (pin "24") (pinfunction "I/O_24") (pintype "bidirectional"))
    )
    (net (code "222") (name "unconnected-(U11-I{slash}O-Pad27)") (class "Default")
      (node (ref "U11") (pin "27") (pinfunction "I/O_27") (pintype "bidirectional"))
    )
    (net (code "223") (name "unconnected-(U11-I{slash}O-Pad135)") (class "Default")
      (node (ref "U11") (pin "135") (pinfunction "I/O_135") (pintype "bidirectional"))
    )
    (net (code "224") (name "unconnected-(U11-I{slash}O-Pad146)") (class "Default")
      (node (ref "U11") (pin "146") (pinfunction "I/O_146") (pintype "bidirectional"))
    )
    (net (code "225") (name "unconnected-(U11-I{slash}O-Pad166)") (class "Default")
      (node (ref "U11") (pin "166") (pinfunction "I/O_166") (pintype "bidirectional"))
    )
    (net (code "226") (name "unconnected-(U11-I{slash}O-Pad167)") (class "Default")
      (node (ref "U11") (pin "167") (pinfunction "I/O_167") (pintype "bidirectional"))
    )
    (net (code "227") (name "unconnected-(U11-I{slash}O-Pad171)") (class "Default")
      (node (ref "U11") (pin "171") (pinfunction "I/O_171") (pintype "bidirectional"))
    )
    (net (code "228") (name "unconnected-(U11-I{slash}O-Pad172)") (class "Default")
      (node (ref "U11") (pin "172") (pinfunction "I/O_172") (pintype "bidirectional"))
    )
    (net (code "229") (name "unconnected-(U11-I{slash}O-Pad175)") (class "Default")
      (node (ref "U11") (pin "175") (pinfunction "I/O_175") (pintype "bidirectional"))
    )
    (net (code "230") (name "unconnected-(U11-I{slash}O-Pad177)") (class "Default")
      (node (ref "U11") (pin "177") (pinfunction "I/O_177") (pintype "bidirectional"))
    )
    (net (code "231") (name "unconnected-(U11-NC-Pad1)") (class "Default")
      (node (ref "U11") (pin "1") (pinfunction "NC_1") (pintype "bidirectional"))
    )
    (net (code "232") (name "unconnected-(U11-NC-Pad2)") (class "Default")
      (node (ref "U11") (pin "2") (pinfunction "NC_2") (pintype "bidirectional"))
    )
    (net (code "233") (name "unconnected-(U11-NC-Pad51)") (class "Default")
      (node (ref "U11") (pin "51") (pinfunction "NC_51") (pintype "bidirectional"))
    )
    (net (code "234") (name "unconnected-(U11-NC-Pad52)") (class "Default")
      (node (ref "U11") (pin "52") (pinfunction "NC_52") (pintype "bidirectional"))
    )
    (net (code "235") (name "unconnected-(U11-NC-Pad53)") (class "Default")
      (node (ref "U11") (pin "53") (pinfunction "NC_53") (pintype "bidirectional"))
    )
    (net (code "236") (name "unconnected-(U11-NC-Pad54)") (class "Default")
      (node (ref "U11") (pin "54") (pinfunction "NC_54") (pintype "bidirectional"))
    )
    (net (code "237") (name "unconnected-(U11-NC-Pad103)") (class "Default")
      (node (ref "U11") (pin "103") (pinfunction "NC_103") (pintype "bidirectional"))
    )
    (net (code "238") (name "unconnected-(U11-NC-Pad104)") (class "Default")
      (node (ref "U11") (pin "104") (pinfunction "NC_104") (pintype "bidirectional"))
    )
    (net (code "239") (name "unconnected-(U11-NC-Pad105)") (class "Default")
      (node (ref "U11") (pin "105") (pinfunction "NC_105") (pintype "bidirectional"))
    )
    (net (code "240") (name "unconnected-(U11-NC-Pad106)") (class "Default")
      (node (ref "U11") (pin "106") (pinfunction "NC_106") (pintype "bidirectional"))
    )
    (net (code "241") (name "unconnected-(U11-NC-Pad155)") (class "Default")
      (node (ref "U11") (pin "155") (pinfunction "NC_155") (pintype "bidirectional"))
    )
    (net (code "242") (name "unconnected-(U11-NC-Pad156)") (class "Default")
      (node (ref "U11") (pin "156") (pinfunction "NC_156") (pintype "bidirectional"))
    )
    (net (code "243") (name "unconnected-(U11-NC-Pad157)") (class "Default")
      (node (ref "U11") (pin "157") (pinfunction "NC_157") (pintype "bidirectional"))
    )
    (net (code "244") (name "unconnected-(U11-NC-Pad158)") (class "Default")
      (node (ref "U11") (pin "158") (pinfunction "NC_158") (pintype "bidirectional"))
    )
    (net (code "245") (name "unconnected-(U11-NC-Pad207)") (class "Default")
      (node (ref "U11") (pin "207") (pinfunction "NC_207") (pintype "bidirectional"))
    )
    (net (code "246") (name "unconnected-(U11-NC-Pad208)") (class "Default")
      (node (ref "U11") (pin "208") (pinfunction "NC_208") (pintype "bidirectional"))
    )
    (net (code "247") (name "unconnected-(UR5-Pad1)") (class "Default")
      (node (ref "UR5") (pin "1") (pinfunction "1_1") (pintype "passive"))
    )
    (net (code "248") (name "unconnected-(UR6-Pad1)") (class "Default")
      (node (ref "UR6") (pin "1") (pinfunction "1_1") (pintype "passive"))
    )
    (net (code "249") (name "unconnected-(UR7-Pad1)") (class "Default")
      (node (ref "UR7") (pin "1") (pinfunction "1_1") (pintype "passive"))
    )
    (net (code "250") (name "unconnected-(UR8-Pad1)") (class "Default")
      (node (ref "UR8") (pin "1") (pinfunction "1_1") (pintype "passive"))
    )
    (net (code "251") (name "unconnected-(UR9-Pad1)") (class "Default")
      (node (ref "UR9") (pin "1") (pinfunction "1_1") (pintype "passive"))
    )
    (net (code "252") (name "unconnected-(UR10-Pad1)") (class "Default")
      (node (ref "UR10") (pin "1") (pinfunction "1_1") (pintype "passive"))
    )
    (net (code "253") (name "unconnected-(UR11-Pad1)") (class "Default")
      (node (ref "UR11") (pin "1") (pinfunction "1_1") (pintype "passive"))
    )
    (net (code "254") (name "unconnected-(UR12-Pad1)") (class "Default")
      (node (ref "UR12") (pin "1") (pinfunction "1_1") (pintype "passive"))
    )
  )
)
